# axiom_beta_sensor_cmv12000_v0_12_aa9cc54.net
KiCad netlist of a schematic drawn in EAGLE
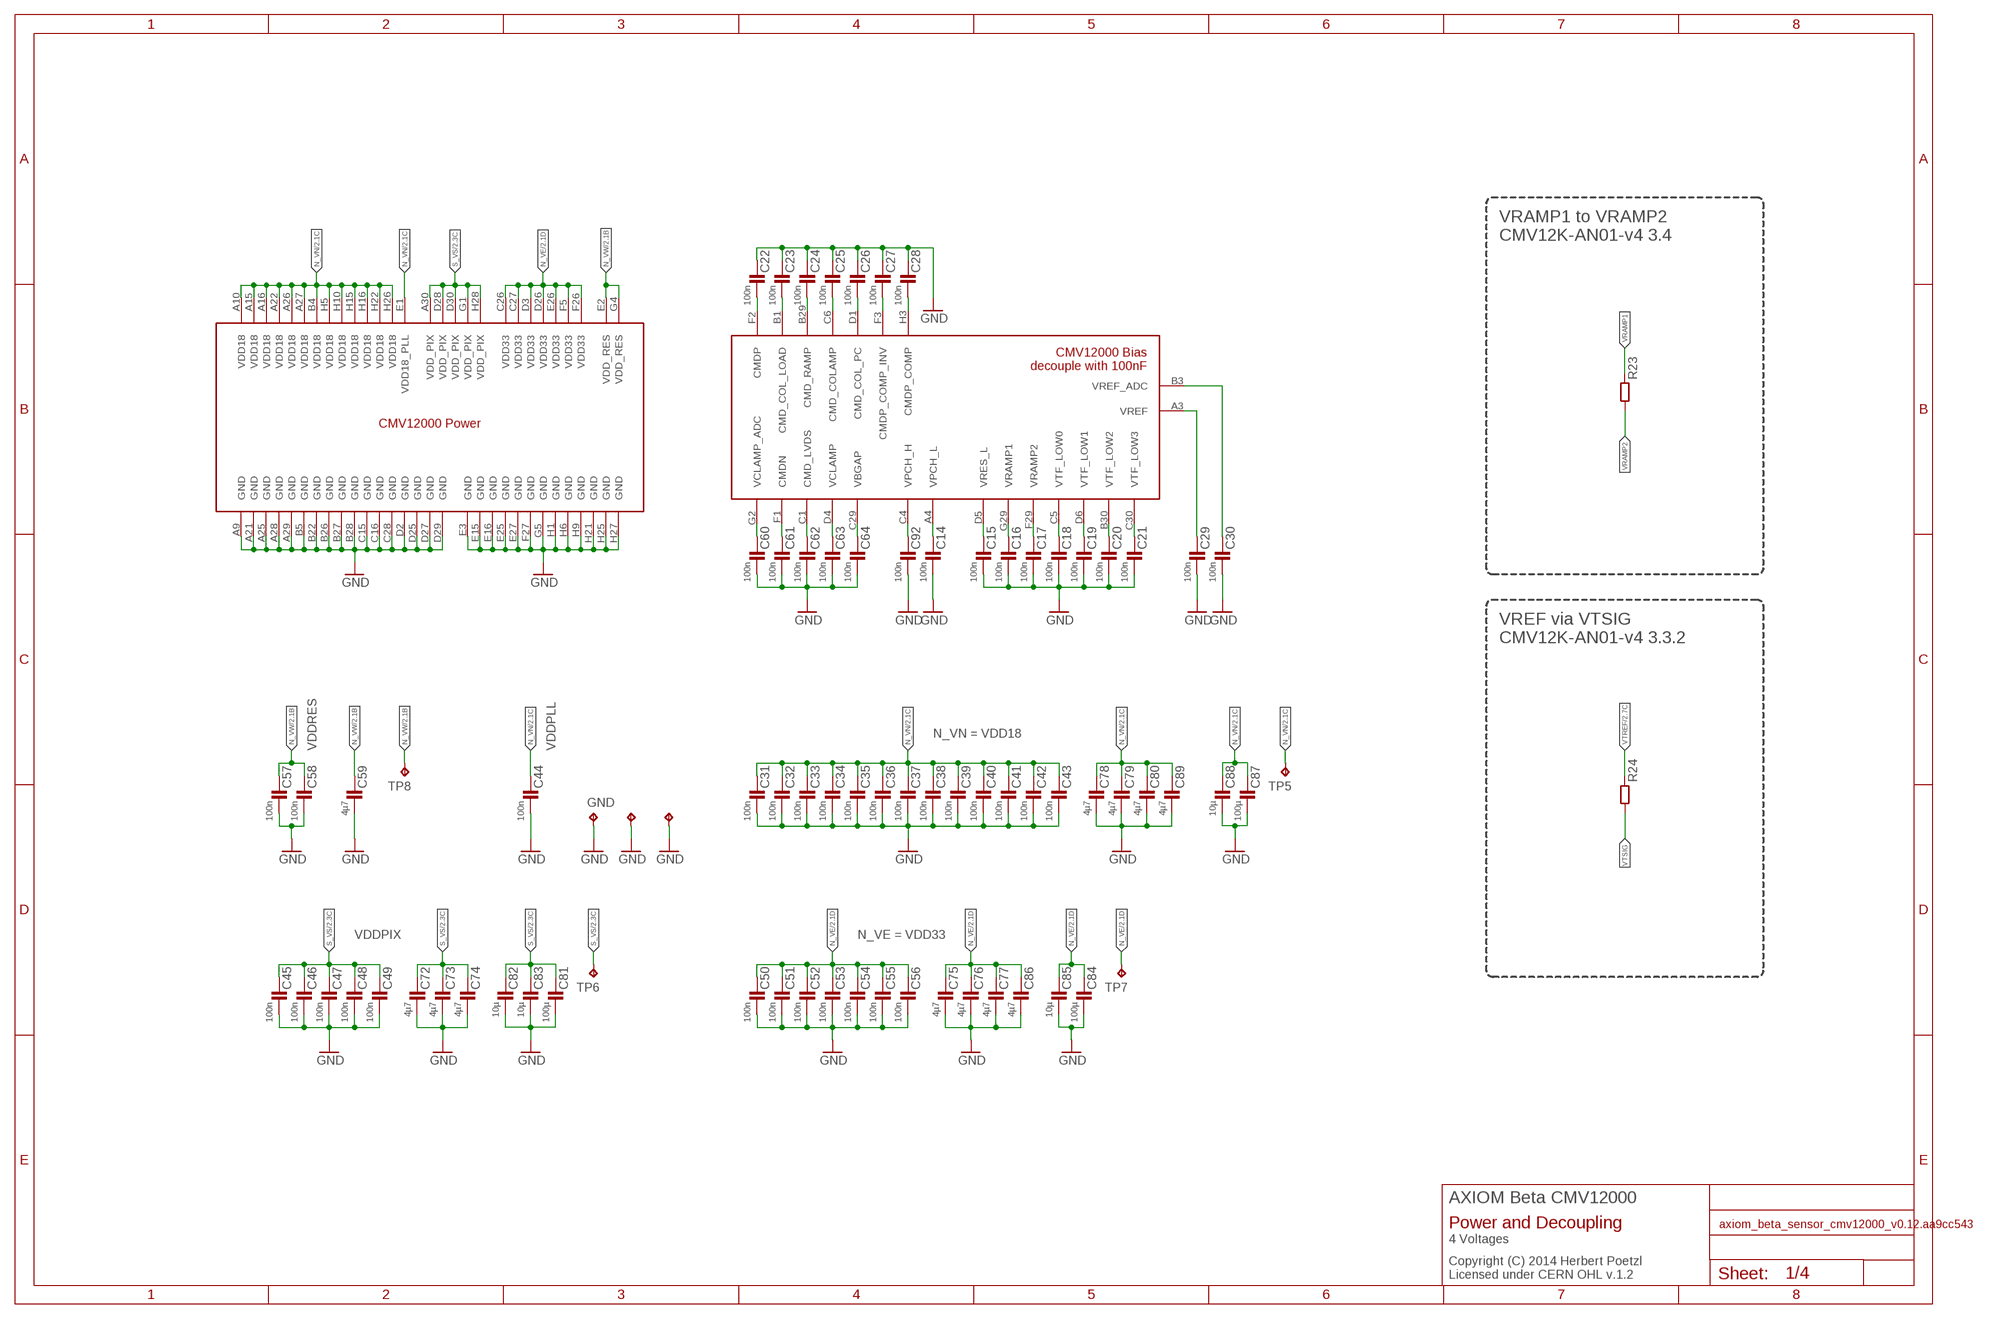
[diagram p0: schematic, sheet 1]
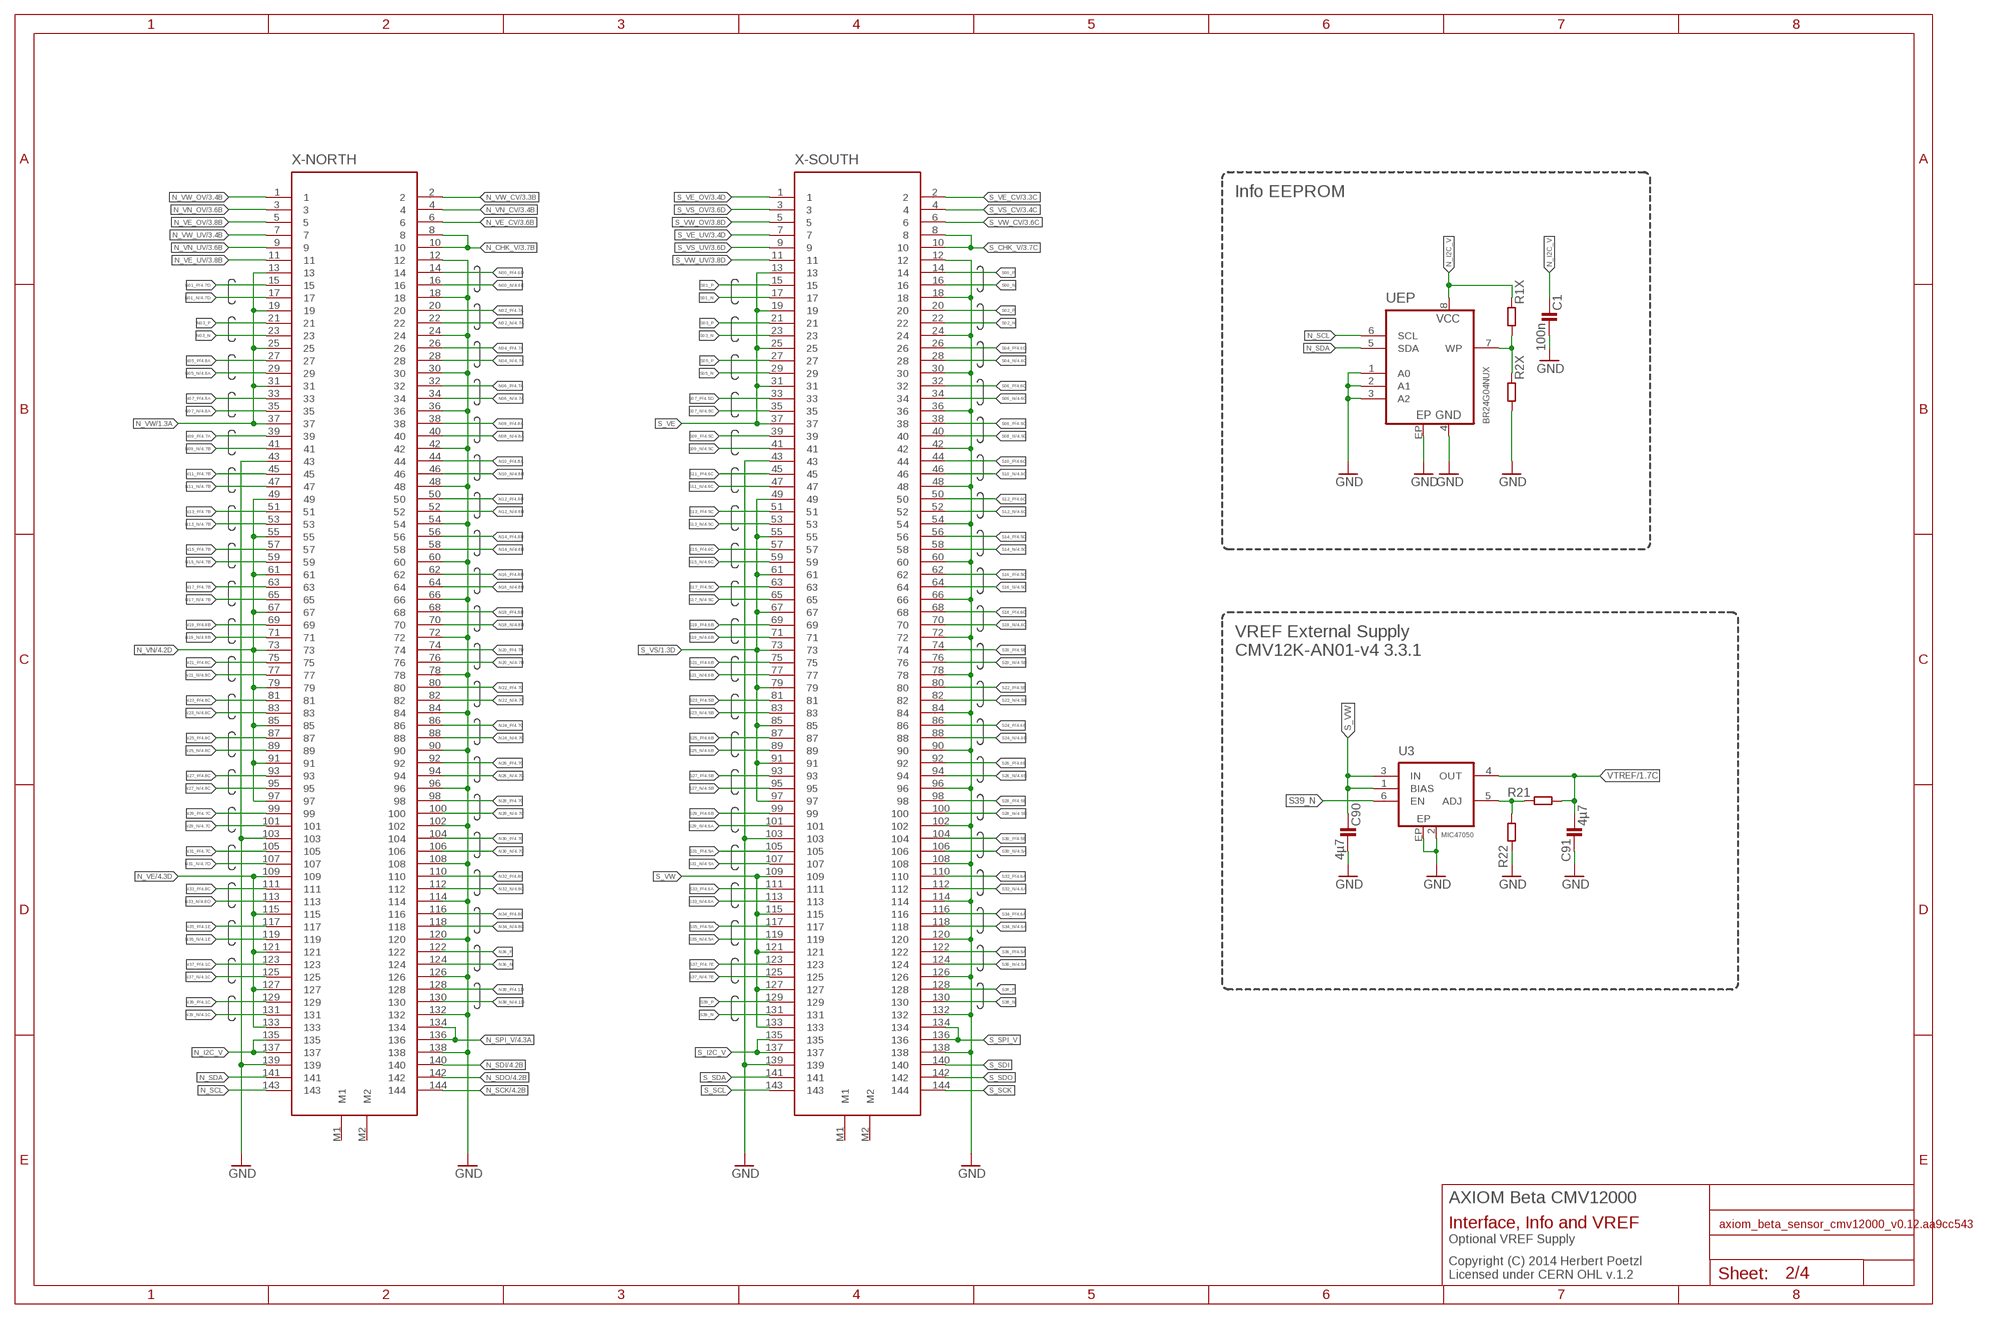
[diagram p1: schematic, sheet 2]
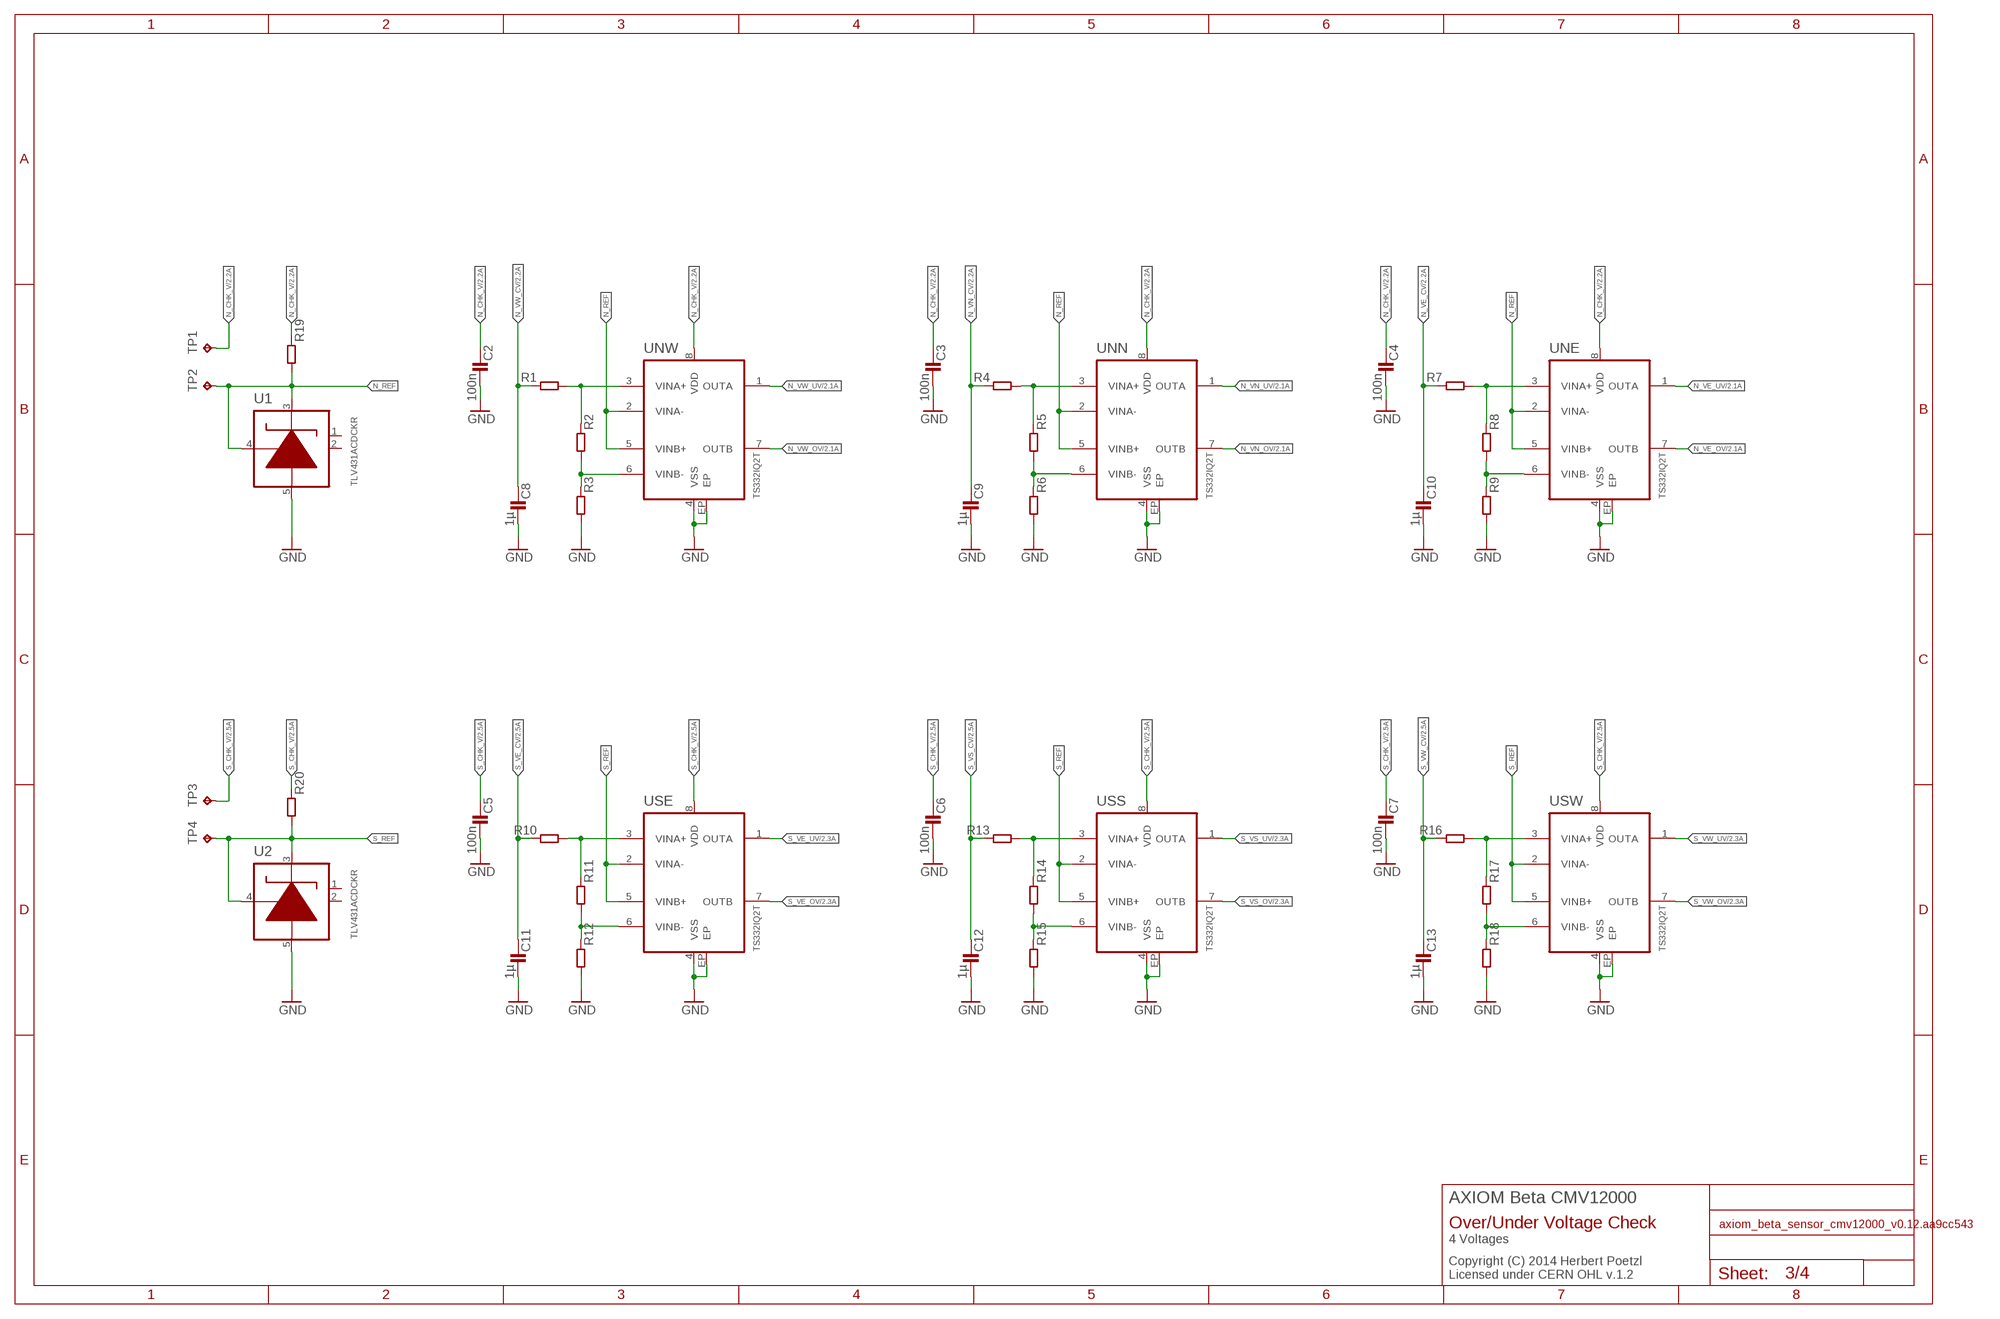
[diagram p2: schematic, sheet 3]
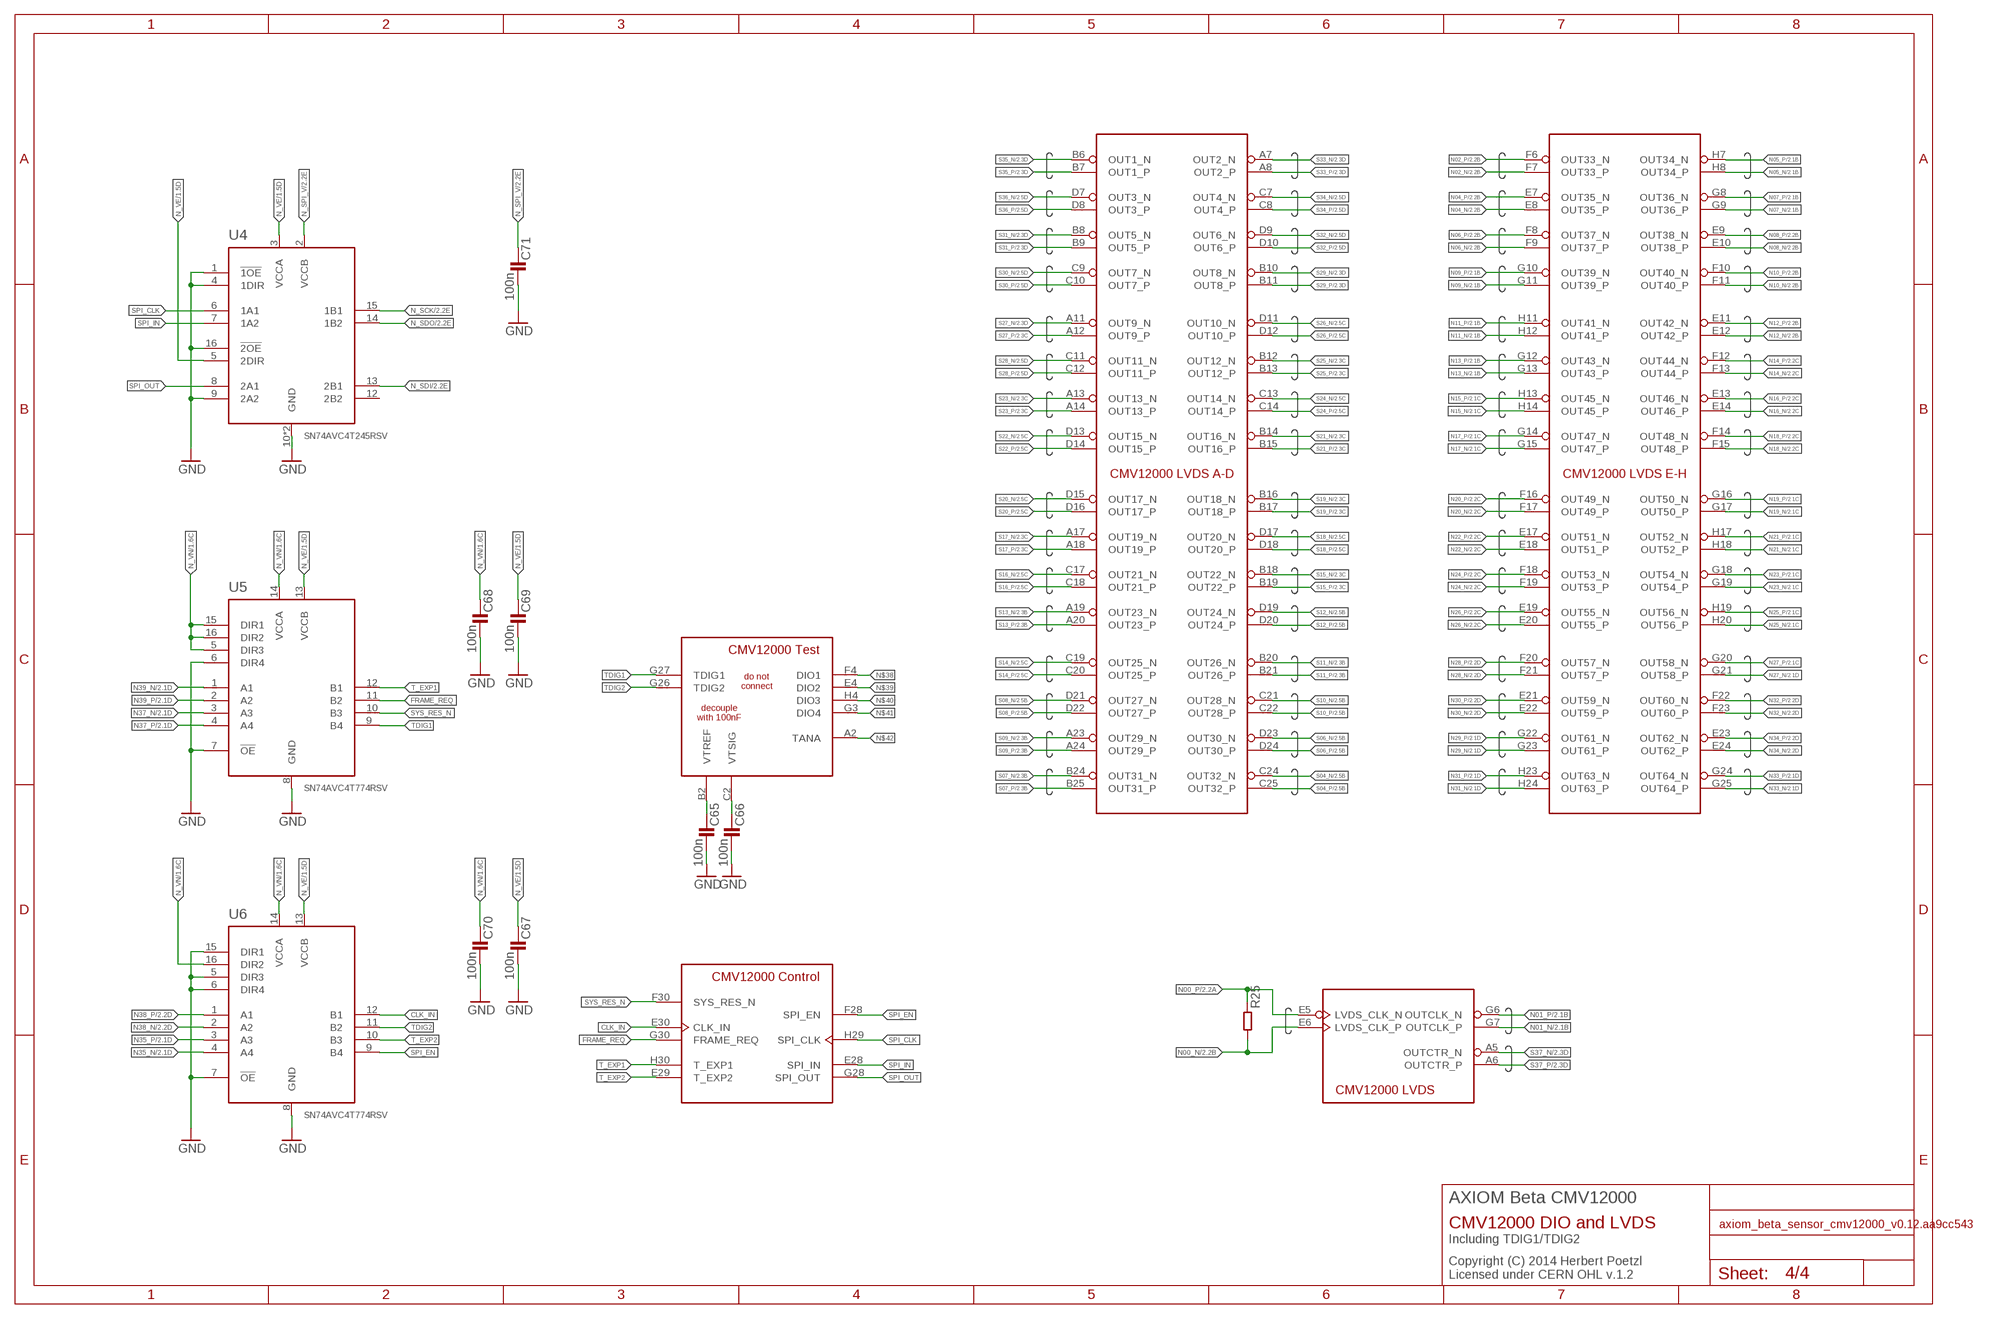
[diagram p3: schematic, sheet 4]

(export (version "E")
  (design (tool "Eeschema 10.0.6"))
  (components
    (comp (ref "C65")
      (value "100n")
      (footprint "eagle-import:0402-C")
      (libsource (lib "eagle-import") (part "C0402-C"))
    )
    (comp (ref "C66")
      (value "100n")
      (footprint "eagle-import:0402-C")
      (libsource (lib "eagle-import") (part "C0402-C"))
    )
    (comp (ref "C67")
      (value "100n")
      (footprint "eagle-import:0402-C")
      (libsource (lib "eagle-import") (part "C0402-C"))
    )
    (comp (ref "C68")
      (value "100n")
      (footprint "eagle-import:0402-C")
      (libsource (lib "eagle-import") (part "C0402-C"))
    )
    (comp (ref "C69")
      (value "100n")
      (footprint "eagle-import:0402-C")
      (libsource (lib "eagle-import") (part "C0402-C"))
    )
    (comp (ref "C70")
      (value "100n")
      (footprint "eagle-import:0402-C")
      (libsource (lib "eagle-import") (part "C0402-C"))
    )
    (comp (ref "C71")
      (value "100n")
      (footprint "eagle-import:0402-C")
      (libsource (lib "eagle-import") (part "C0402-C"))
    )
    (comp (ref "R25")
      (value "R0402-C")
      (footprint "eagle-import:0402-C")
      (libsource (lib "eagle-import") (part "R0402-C"))
    )
    (comp (ref "SENSOR")
      (value "CMV12000ANDON")
      (footprint "eagle-import:10-30-07-237-400T4")
      (libsource (lib "eagle-import") (part "CMV12000ANDON"))
    )
    (comp (ref "U4")
      (value "SN74AVC4T245RSV")
      (footprint "eagle-import:QFN40P185X265X55-16N")
      (libsource (lib "eagle-import") (part "SN74AVC4T245RSV"))
    )
    (comp (ref "U5")
      (value "SN74AVC4T774RSV")
      (footprint "eagle-import:QFN40P185X265X55-16N")
      (libsource (lib "eagle-import") (part "SN74AVC4T774RSV"))
    )
    (comp (ref "U6")
      (value "SN74AVC4T774RSV")
      (footprint "eagle-import:QFN40P185X265X55-16N")
      (libsource (lib "eagle-import") (part "SN74AVC4T774RSV"))
    )
    (comp (ref "C2")
      (value "100n")
      (footprint "eagle-import:0402-C")
      (libsource (lib "eagle-import") (part "C0402-C"))
    )
    (comp (ref "C3")
      (value "100n")
      (footprint "eagle-import:0402-C")
      (libsource (lib "eagle-import") (part "C0402-C"))
    )
    (comp (ref "C4")
      (value "100n")
      (footprint "eagle-import:0402-C")
      (libsource (lib "eagle-import") (part "C0402-C"))
    )
    (comp (ref "C5")
      (value "100n")
      (footprint "eagle-import:0402-C")
      (libsource (lib "eagle-import") (part "C0402-C"))
    )
    (comp (ref "C6")
      (value "100n")
      (footprint "eagle-import:0402-C")
      (libsource (lib "eagle-import") (part "C0402-C"))
    )
    (comp (ref "C7")
      (value "100n")
      (footprint "eagle-import:0402-C")
      (libsource (lib "eagle-import") (part "C0402-C"))
    )
    (comp (ref "C8")
      (value "1µ")
      (footprint "eagle-import:0402-C")
      (libsource (lib "eagle-import") (part "C0402-C"))
    )
    (comp (ref "C9")
      (value "1µ")
      (footprint "eagle-import:0402-C")
      (libsource (lib "eagle-import") (part "C0402-C"))
    )
    (comp (ref "C10")
      (value "1µ")
      (footprint "eagle-import:0402-C")
      (libsource (lib "eagle-import") (part "C0402-C"))
    )
    (comp (ref "C11")
      (value "1µ")
      (footprint "eagle-import:0402-C")
      (libsource (lib "eagle-import") (part "C0402-C"))
    )
    (comp (ref "C12")
      (value "1µ")
      (footprint "eagle-import:0402-C")
      (libsource (lib "eagle-import") (part "C0402-C"))
    )
    (comp (ref "C13")
      (value "1µ")
      (footprint "eagle-import:0402-C")
      (libsource (lib "eagle-import") (part "C0402-C"))
    )
    (comp (ref "R1")
      (value "R0402-C")
      (footprint "eagle-import:0402-C")
      (libsource (lib "eagle-import") (part "R0402-C"))
    )
    (comp (ref "R2")
      (value "R0402-C")
      (footprint "eagle-import:0402-C")
      (libsource (lib "eagle-import") (part "R0402-C"))
    )
    (comp (ref "R3")
      (value "R0402-C")
      (footprint "eagle-import:0402-C")
      (libsource (lib "eagle-import") (part "R0402-C"))
    )
    (comp (ref "R4")
      (value "R0402-C")
      (footprint "eagle-import:0402-C")
      (libsource (lib "eagle-import") (part "R0402-C"))
    )
    (comp (ref "R5")
      (value "R0402-C")
      (footprint "eagle-import:0402-C")
      (libsource (lib "eagle-import") (part "R0402-C"))
    )
    (comp (ref "R6")
      (value "R0402-C")
      (footprint "eagle-import:0402-C")
      (libsource (lib "eagle-import") (part "R0402-C"))
    )
    (comp (ref "R7")
      (value "R0402-C")
      (footprint "eagle-import:0402-C")
      (libsource (lib "eagle-import") (part "R0402-C"))
    )
    (comp (ref "R8")
      (value "R0402-C")
      (footprint "eagle-import:0402-C")
      (libsource (lib "eagle-import") (part "R0402-C"))
    )
    (comp (ref "R9")
      (value "R0402-C")
      (footprint "eagle-import:0402-C")
      (libsource (lib "eagle-import") (part "R0402-C"))
    )
    (comp (ref "R10")
      (value "R0402-C")
      (footprint "eagle-import:0402-C")
      (libsource (lib "eagle-import") (part "R0402-C"))
    )
    (comp (ref "R11")
      (value "R0402-C")
      (footprint "eagle-import:0402-C")
      (libsource (lib "eagle-import") (part "R0402-C"))
    )
    (comp (ref "R12")
      (value "R0402-C")
      (footprint "eagle-import:0402-C")
      (libsource (lib "eagle-import") (part "R0402-C"))
    )
    (comp (ref "R13")
      (value "R0402-C")
      (footprint "eagle-import:0402-C")
      (libsource (lib "eagle-import") (part "R0402-C"))
    )
    (comp (ref "R14")
      (value "R0402-C")
      (footprint "eagle-import:0402-C")
      (libsource (lib "eagle-import") (part "R0402-C"))
    )
    (comp (ref "R15")
      (value "R0402-C")
      (footprint "eagle-import:0402-C")
      (libsource (lib "eagle-import") (part "R0402-C"))
    )
    (comp (ref "R16")
      (value "R0402-C")
      (footprint "eagle-import:0402-C")
      (libsource (lib "eagle-import") (part "R0402-C"))
    )
    (comp (ref "R17")
      (value "R0402-C")
      (footprint "eagle-import:0402-C")
      (libsource (lib "eagle-import") (part "R0402-C"))
    )
    (comp (ref "R18")
      (value "R0402-C")
      (footprint "eagle-import:0402-C")
      (libsource (lib "eagle-import") (part "R0402-C"))
    )
    (comp (ref "R19")
      (value "R0402-C")
      (footprint "eagle-import:0402-C")
      (libsource (lib "eagle-import") (part "R0402-C"))
    )
    (comp (ref "R20")
      (value "R0402-C")
      (footprint "eagle-import:0402-C")
      (libsource (lib "eagle-import") (part "R0402-C"))
    )
    (comp (ref "TP1")
      (value "TPTP10R")
      (footprint "eagle-import:TP10R")
      (libsource (lib "eagle-import") (part "TPTP10R"))
    )
    (comp (ref "TP2")
      (value "TPTP10R")
      (footprint "eagle-import:TP10R")
      (libsource (lib "eagle-import") (part "TPTP10R"))
    )
    (comp (ref "TP3")
      (value "TPTP10R")
      (footprint "eagle-import:TP10R")
      (libsource (lib "eagle-import") (part "TPTP10R"))
    )
    (comp (ref "TP4")
      (value "TPTP10R")
      (footprint "eagle-import:TP10R")
      (libsource (lib "eagle-import") (part "TPTP10R"))
    )
    (comp (ref "U1")
      (value "TLV431ACDCKR")
      (footprint "eagle-import:SOT65P210X110-5N")
      (libsource (lib "eagle-import") (part "TLV431ACDCKR"))
    )
    (comp (ref "U2")
      (value "TLV431ACDCKR")
      (footprint "eagle-import:SOT65P210X110-5N")
      (libsource (lib "eagle-import") (part "TLV431ACDCKR"))
    )
    (comp (ref "UNE")
      (value "TS332IQ2T")
      (footprint "eagle-import:DFN200X200X100-9N")
      (libsource (lib "eagle-import") (part "TS332IQ2T"))
    )
    (comp (ref "UNN")
      (value "TS332IQ2T")
      (footprint "eagle-import:DFN200X200X100-9N")
      (libsource (lib "eagle-import") (part "TS332IQ2T"))
    )
    (comp (ref "UNW")
      (value "TS332IQ2T")
      (footprint "eagle-import:DFN200X200X100-9N")
      (libsource (lib "eagle-import") (part "TS332IQ2T"))
    )
    (comp (ref "USE")
      (value "TS332IQ2T")
      (footprint "eagle-import:DFN200X200X100-9N")
      (libsource (lib "eagle-import") (part "TS332IQ2T"))
    )
    (comp (ref "USS")
      (value "TS332IQ2T")
      (footprint "eagle-import:DFN200X200X100-9N")
      (libsource (lib "eagle-import") (part "TS332IQ2T"))
    )
    (comp (ref "USW")
      (value "TS332IQ2T")
      (footprint "eagle-import:DFN200X200X100-9N")
      (libsource (lib "eagle-import") (part "TS332IQ2T"))
    )
    (comp (ref "C1")
      (value "100n")
      (footprint "eagle-import:0402-C")
      (libsource (lib "eagle-import") (part "C0402-C"))
    )
    (comp (ref "C90")
      (value "4µ7")
      (footprint "eagle-import:0402-C")
      (libsource (lib "eagle-import") (part "C0402-C"))
    )
    (comp (ref "C91")
      (value "4µ7")
      (footprint "eagle-import:0402-C")
      (libsource (lib "eagle-import") (part "C0402-C"))
    )
    (comp (ref "R1X")
      (value "R0402-C")
      (footprint "eagle-import:0402-C")
      (libsource (lib "eagle-import") (part "R0402-C"))
    )
    (comp (ref "R2X")
      (value "R0402-C")
      (footprint "eagle-import:0402-C")
      (libsource (lib "eagle-import") (part "R0402-C"))
    )
    (comp (ref "R21")
      (value "R0402-C")
      (footprint "eagle-import:0402-C")
      (libsource (lib "eagle-import") (part "R0402-C"))
    )
    (comp (ref "R22")
      (value "R0402-C")
      (footprint "eagle-import:0402-C")
      (libsource (lib "eagle-import") (part "R0402-C"))
    )
    (comp (ref "U3")
      (value "MIC47050")
      (footprint "eagle-import:MLF-6")
      (libsource (lib "eagle-import") (part "MIC47050-ADJ"))
    )
    (comp (ref "UEP")
      (value "BR24G04NUX")
      (footprint "eagle-import:DFN200X300X100-9N")
      (libsource (lib "eagle-import") (part "BR24G04NUX"))
    )
    (comp (ref "X-NORTH")
      (value "FX10-144P")
      (footprint "eagle-import:FX10A-144P")
      (libsource (lib "eagle-import") (part "FX10-144P"))
    )
    (comp (ref "X-SOUTH")
      (value "FX10-144P")
      (footprint "eagle-import:FX10A-144P")
      (libsource (lib "eagle-import") (part "FX10-144P"))
    )
    (comp (ref "C14")
      (value "100n")
      (footprint "eagle-import:0402-C")
      (libsource (lib "eagle-import") (part "C0402-C"))
    )
    (comp (ref "C15")
      (value "100n")
      (footprint "eagle-import:0402-C")
      (libsource (lib "eagle-import") (part "C0402-C"))
    )
    (comp (ref "C16")
      (value "100n")
      (footprint "eagle-import:0402-C")
      (libsource (lib "eagle-import") (part "C0402-C"))
    )
    (comp (ref "C17")
      (value "100n")
      (footprint "eagle-import:0402-C")
      (libsource (lib "eagle-import") (part "C0402-C"))
    )
    (comp (ref "C18")
      (value "100n")
      (footprint "eagle-import:0402-C")
      (libsource (lib "eagle-import") (part "C0402-C"))
    )
    (comp (ref "C19")
      (value "100n")
      (footprint "eagle-import:0402-C")
      (libsource (lib "eagle-import") (part "C0402-C"))
    )
    (comp (ref "C20")
      (value "100n")
      (footprint "eagle-import:0402-C")
      (libsource (lib "eagle-import") (part "C0402-C"))
    )
    (comp (ref "C21")
      (value "100n")
      (footprint "eagle-import:0402-C")
      (libsource (lib "eagle-import") (part "C0402-C"))
    )
    (comp (ref "C22")
      (value "100n")
      (footprint "eagle-import:0402-C")
      (libsource (lib "eagle-import") (part "C0402-C"))
    )
    (comp (ref "C23")
      (value "100n")
      (footprint "eagle-import:0402-C")
      (libsource (lib "eagle-import") (part "C0402-C"))
    )
    (comp (ref "C24")
      (value "100n")
      (footprint "eagle-import:0402-C")
      (libsource (lib "eagle-import") (part "C0402-C"))
    )
    (comp (ref "C25")
      (value "100n")
      (footprint "eagle-import:0402-C")
      (libsource (lib "eagle-import") (part "C0402-C"))
    )
    (comp (ref "C26")
      (value "100n")
      (footprint "eagle-import:0402-C")
      (libsource (lib "eagle-import") (part "C0402-C"))
    )
    (comp (ref "C27")
      (value "100n")
      (footprint "eagle-import:0402-C")
      (libsource (lib "eagle-import") (part "C0402-C"))
    )
    (comp (ref "C28")
      (value "100n")
      (footprint "eagle-import:0402-C")
      (libsource (lib "eagle-import") (part "C0402-C"))
    )
    (comp (ref "C29")
      (value "100n")
      (footprint "eagle-import:0402-C")
      (libsource (lib "eagle-import") (part "C0402-C"))
    )
    (comp (ref "C30")
      (value "100n")
      (footprint "eagle-import:0402-C")
      (libsource (lib "eagle-import") (part "C0402-C"))
    )
    (comp (ref "C31")
      (value "100n")
      (footprint "eagle-import:0402-C")
      (libsource (lib "eagle-import") (part "C0402-C"))
    )
    (comp (ref "C32")
      (value "100n")
      (footprint "eagle-import:0402-C")
      (libsource (lib "eagle-import") (part "C0402-C"))
    )
    (comp (ref "C33")
      (value "100n")
      (footprint "eagle-import:0402-C")
      (libsource (lib "eagle-import") (part "C0402-C"))
    )
    (comp (ref "C34")
      (value "100n")
      (footprint "eagle-import:0402-C")
      (libsource (lib "eagle-import") (part "C0402-C"))
    )
    (comp (ref "C35")
      (value "100n")
      (footprint "eagle-import:0402-C")
      (libsource (lib "eagle-import") (part "C0402-C"))
    )
    (comp (ref "C36")
      (value "100n")
      (footprint "eagle-import:0402-C")
      (libsource (lib "eagle-import") (part "C0402-C"))
    )
    (comp (ref "C37")
      (value "100n")
      (footprint "eagle-import:0402-C")
      (libsource (lib "eagle-import") (part "C0402-C"))
    )
    (comp (ref "C38")
      (value "100n")
      (footprint "eagle-import:0402-C")
      (libsource (lib "eagle-import") (part "C0402-C"))
    )
    (comp (ref "C39")
      (value "100n")
      (footprint "eagle-import:0402-C")
      (libsource (lib "eagle-import") (part "C0402-C"))
    )
    (comp (ref "C40")
      (value "100n")
      (footprint "eagle-import:0402-C")
      (libsource (lib "eagle-import") (part "C0402-C"))
    )
    (comp (ref "C41")
      (value "100n")
      (footprint "eagle-import:0402-C")
      (libsource (lib "eagle-import") (part "C0402-C"))
    )
    (comp (ref "C42")
      (value "100n")
      (footprint "eagle-import:0402-C")
      (libsource (lib "eagle-import") (part "C0402-C"))
    )
    (comp (ref "C43")
      (value "100n")
      (footprint "eagle-import:0402-C")
      (libsource (lib "eagle-import") (part "C0402-C"))
    )
    (comp (ref "C44")
      (value "100n")
      (footprint "eagle-import:0402-C")
      (libsource (lib "eagle-import") (part "C0402-C"))
    )
    (comp (ref "C45")
      (value "100n")
      (footprint "eagle-import:0402-C")
      (libsource (lib "eagle-import") (part "C0402-C"))
    )
    (comp (ref "C46")
      (value "100n")
      (footprint "eagle-import:0402-C")
      (libsource (lib "eagle-import") (part "C0402-C"))
    )
    (comp (ref "C47")
      (value "100n")
      (footprint "eagle-import:0402-C")
      (libsource (lib "eagle-import") (part "C0402-C"))
    )
    (comp (ref "C48")
      (value "100n")
      (footprint "eagle-import:0402-C")
      (libsource (lib "eagle-import") (part "C0402-C"))
    )
    (comp (ref "C49")
      (value "100n")
      (footprint "eagle-import:0402-C")
      (libsource (lib "eagle-import") (part "C0402-C"))
    )
    (comp (ref "C50")
      (value "100n")
      (footprint "eagle-import:0402-C")
      (libsource (lib "eagle-import") (part "C0402-C"))
    )
    (comp (ref "C51")
      (value "100n")
      (footprint "eagle-import:0402-C")
      (libsource (lib "eagle-import") (part "C0402-C"))
    )
    (comp (ref "C52")
      (value "100n")
      (footprint "eagle-import:0402-C")
      (libsource (lib "eagle-import") (part "C0402-C"))
    )
    (comp (ref "C53")
      (value "100n")
      (footprint "eagle-import:0402-C")
      (libsource (lib "eagle-import") (part "C0402-C"))
    )
    (comp (ref "C54")
      (value "100n")
      (footprint "eagle-import:0402-C")
      (libsource (lib "eagle-import") (part "C0402-C"))
    )
    (comp (ref "C55")
      (value "100n")
      (footprint "eagle-import:0402-C")
      (libsource (lib "eagle-import") (part "C0402-C"))
    )
    (comp (ref "C56")
      (value "100n")
      (footprint "eagle-import:0402-C")
      (libsource (lib "eagle-import") (part "C0402-C"))
    )
    (comp (ref "C57")
      (value "100n")
      (footprint "eagle-import:0402-C")
      (libsource (lib "eagle-import") (part "C0402-C"))
    )
    (comp (ref "C58")
      (value "100n")
      (footprint "eagle-import:0402-C")
      (libsource (lib "eagle-import") (part "C0402-C"))
    )
    (comp (ref "C59")
      (value "4µ7")
      (footprint "eagle-import:0402-C")
      (libsource (lib "eagle-import") (part "C0402-C"))
    )
    (comp (ref "C60")
      (value "100n")
      (footprint "eagle-import:0402-C")
      (libsource (lib "eagle-import") (part "C0402-C"))
    )
    (comp (ref "C61")
      (value "100n")
      (footprint "eagle-import:0402-C")
      (libsource (lib "eagle-import") (part "C0402-C"))
    )
    (comp (ref "C62")
      (value "100n")
      (footprint "eagle-import:0402-C")
      (libsource (lib "eagle-import") (part "C0402-C"))
    )
    (comp (ref "C63")
      (value "100n")
      (footprint "eagle-import:0402-C")
      (libsource (lib "eagle-import") (part "C0402-C"))
    )
    (comp (ref "C64")
      (value "100n")
      (footprint "eagle-import:0402-C")
      (libsource (lib "eagle-import") (part "C0402-C"))
    )
    (comp (ref "C72")
      (value "4µ7")
      (footprint "eagle-import:0402-B")
      (libsource (lib "eagle-import") (part "C0402-B"))
    )
    (comp (ref "C73")
      (value "4µ7")
      (footprint "eagle-import:0402-C")
      (libsource (lib "eagle-import") (part "C0402-C"))
    )
    (comp (ref "C74")
      (value "4µ7")
      (footprint "eagle-import:0402-C")
      (libsource (lib "eagle-import") (part "C0402-C"))
    )
    (comp (ref "C75")
      (value "4µ7")
      (footprint "eagle-import:0402-C")
      (libsource (lib "eagle-import") (part "C0402-C"))
    )
    (comp (ref "C76")
      (value "4µ7")
      (footprint "eagle-import:0402-C")
      (libsource (lib "eagle-import") (part "C0402-C"))
    )
    (comp (ref "C77")
      (value "4µ7")
      (footprint "eagle-import:0402-B")
      (libsource (lib "eagle-import") (part "C0402-B"))
    )
    (comp (ref "C78")
      (value "4µ7")
      (footprint "eagle-import:0402-B")
      (libsource (lib "eagle-import") (part "C0402-B"))
    )
    (comp (ref "C79")
      (value "4µ7")
      (footprint "eagle-import:0402-C")
      (libsource (lib "eagle-import") (part "C0402-C"))
    )
    (comp (ref "C80")
      (value "4µ7")
      (footprint "eagle-import:0402-C")
      (libsource (lib "eagle-import") (part "C0402-C"))
    )
    (comp (ref "C81")
      (value "100µ")
      (footprint "eagle-import:1206-B")
      (libsource (lib "eagle-import") (part "C1206-B"))
    )
    (comp (ref "C82")
      (value "10µ")
      (footprint "eagle-import:0603-C")
      (libsource (lib "eagle-import") (part "C0603-C"))
    )
    (comp (ref "C83")
      (value "10µ")
      (footprint "eagle-import:0603-C")
      (libsource (lib "eagle-import") (part "C0603-C"))
    )
    (comp (ref "C84")
      (value "100µ")
      (footprint "eagle-import:1206-B")
      (libsource (lib "eagle-import") (part "C1206-B"))
    )
    (comp (ref "C85")
      (value "10µ")
      (footprint "eagle-import:0603-C")
      (libsource (lib "eagle-import") (part "C0603-C"))
    )
    (comp (ref "C86")
      (value "4µ7")
      (footprint "eagle-import:0402-C")
      (libsource (lib "eagle-import") (part "C0402-C"))
    )
    (comp (ref "C87")
      (value "100µ")
      (footprint "eagle-import:1206-B")
      (libsource (lib "eagle-import") (part "C1206-B"))
    )
    (comp (ref "C88")
      (value "10µ")
      (footprint "eagle-import:0603-C")
      (libsource (lib "eagle-import") (part "C0603-C"))
    )
    (comp (ref "C89")
      (value "4µ7")
      (footprint "eagle-import:0402-C")
      (libsource (lib "eagle-import") (part "C0402-C"))
    )
    (comp (ref "C92")
      (value "100n")
      (footprint "eagle-import:0402-C")
      (libsource (lib "eagle-import") (part "C0402-C"))
    )
    (comp (ref "GND")
      (value "TPTP10R")
      (footprint "eagle-import:TP10R")
      (libsource (lib "eagle-import") (part "TPTP10R"))
    )
    (comp (ref "GND75")
      (value "TPTP10R")
      (footprint "eagle-import:TP10R")
      (libsource (lib "eagle-import") (part "TPTP10R"))
    )
    (comp (ref "GND77")
      (value "TPTP10R")
      (footprint "eagle-import:TP10R")
      (libsource (lib "eagle-import") (part "TPTP10R"))
    )
    (comp (ref "R23")
      (value "R0402-C")
      (footprint "eagle-import:0402-C")
      (libsource (lib "eagle-import") (part "R0402-C"))
    )
    (comp (ref "R24")
      (value "R0402-C")
      (footprint "eagle-import:0402-C")
      (libsource (lib "eagle-import") (part "R0402-C"))
    )
    (comp (ref "TP5")
      (value "TPTP10R")
      (footprint "eagle-import:TP10R")
      (libsource (lib "eagle-import") (part "TPTP10R"))
    )
    (comp (ref "TP6")
      (value "TPTP10R")
      (footprint "eagle-import:TP10R")
      (libsource (lib "eagle-import") (part "TPTP10R"))
    )
    (comp (ref "TP7")
      (value "TPTP10R")
      (footprint "eagle-import:TP10R")
      (libsource (lib "eagle-import") (part "TPTP10R"))
    )
    (comp (ref "TP8")
      (value "TPTP10R")
      (footprint "eagle-import:TP10R")
      (libsource (lib "eagle-import") (part "TPTP10R"))
    )
  )
  (nets
    (net (code "1") (name "CLK_IN") (class "Default")
      (node (ref "SENSOR") (pin "E30") (pinfunction "CLK_IN_E30") (pintype "input"))
      (node (ref "U6") (pin "12") (pinfunction "B1_12") (pintype "bidirectional"))
    )
    (net (code "2") (name "FRAME_REQ") (class "Default")
      (node (ref "SENSOR") (pin "G30") (pinfunction "FRAME_REQ_G30") (pintype "input"))
      (node (ref "U5") (pin "11") (pinfunction "B2_11") (pintype "bidirectional"))
    )
    (net (code "3") (name "GND") (class "Default")
      (node (ref "C1") (pin "2") (pinfunction "2_2") (pintype "passive"))
      (node (ref "C10") (pin "2") (pinfunction "2_2") (pintype "passive"))
      (node (ref "C11") (pin "2") (pinfunction "2_2") (pintype "passive"))
      (node (ref "C12") (pin "2") (pinfunction "2_2") (pintype "passive"))
      (node (ref "C13") (pin "2") (pinfunction "2_2") (pintype "passive"))
      (node (ref "C14") (pin "2") (pinfunction "2_2") (pintype "passive"))
      (node (ref "C15") (pin "2") (pinfunction "2_2") (pintype "passive"))
      (node (ref "C16") (pin "2") (pinfunction "2_2") (pintype "passive"))
      (node (ref "C17") (pin "2") (pinfunction "2_2") (pintype "passive"))
      (node (ref "C18") (pin "2") (pinfunction "2_2") (pintype "passive"))
      (node (ref "C19") (pin "2") (pinfunction "2_2") (pintype "passive"))
      (node (ref "C2") (pin "2") (pinfunction "2_2") (pintype "passive"))
      (node (ref "C20") (pin "2") (pinfunction "2_2") (pintype "passive"))
      (node (ref "C21") (pin "2") (pinfunction "2_2") (pintype "passive"))
      (node (ref "C22") (pin "1") (pinfunction "1_1") (pintype "passive"))
      (node (ref "C23") (pin "1") (pinfunction "1_1") (pintype "passive"))
      (node (ref "C24") (pin "1") (pinfunction "1_1") (pintype "passive"))
      (node (ref "C25") (pin "1") (pinfunction "1_1") (pintype "passive"))
      (node (ref "C26") (pin "1") (pinfunction "1_1") (pintype "passive"))
      (node (ref "C27") (pin "1") (pinfunction "1_1") (pintype "passive"))
      (node (ref "C28") (pin "1") (pinfunction "1_1") (pintype "passive"))
      (node (ref "C29") (pin "2") (pinfunction "2_2") (pintype "passive"))
      (node (ref "C3") (pin "2") (pinfunction "2_2") (pintype "passive"))
      (node (ref "C30") (pin "2") (pinfunction "2_2") (pintype "passive"))
      (node (ref "C31") (pin "2") (pinfunction "2_2") (pintype "passive"))
      (node (ref "C32") (pin "2") (pinfunction "2_2") (pintype "passive"))
      (node (ref "C33") (pin "2") (pinfunction "2_2") (pintype "passive"))
      (node (ref "C34") (pin "2") (pinfunction "2_2") (pintype "passive"))
      (node (ref "C35") (pin "2") (pinfunction "2_2") (pintype "passive"))
      (node (ref "C36") (pin "2") (pinfunction "2_2") (pintype "passive"))
      (node (ref "C37") (pin "2") (pinfunction "2_2") (pintype "passive"))
      (node (ref "C38") (pin "2") (pinfunction "2_2") (pintype "passive"))
      (node (ref "C39") (pin "2") (pinfunction "2_2") (pintype "passive"))
      (node (ref "C4") (pin "2") (pinfunction "2_2") (pintype "passive"))
      (node (ref "C40") (pin "2") (pinfunction "2_2") (pintype "passive"))
      (node (ref "C41") (pin "2") (pinfunction "2_2") (pintype "passive"))
      (node (ref "C42") (pin "2") (pinfunction "2_2") (pintype "passive"))
      (node (ref "C43") (pin "2") (pinfunction "2_2") (pintype "passive"))
      (node (ref "C44") (pin "2") (pinfunction "2_2") (pintype "passive"))
      (node (ref "C45") (pin "2") (pinfunction "2_2") (pintype "passive"))
      (node (ref "C46") (pin "2") (pinfunction "2_2") (pintype "passive"))
      (node (ref "C47") (pin "2") (pinfunction "2_2") (pintype "passive"))
      (node (ref "C48") (pin "2") (pinfunction "2_2") (pintype "passive"))
      (node (ref "C49") (pin "2") (pinfunction "2_2") (pintype "passive"))
      (node (ref "C5") (pin "2") (pinfunction "2_2") (pintype "passive"))
      (node (ref "C50") (pin "2") (pinfunction "2_2") (pintype "passive"))
      (node (ref "C51") (pin "2") (pinfunction "2_2") (pintype "passive"))
      (node (ref "C52") (pin "2") (pinfunction "2_2") (pintype "passive"))
      (node (ref "C53") (pin "2") (pinfunction "2_2") (pintype "passive"))
      (node (ref "C54") (pin "2") (pinfunction "2_2") (pintype "passive"))
      (node (ref "C55") (pin "2") (pinfunction "2_2") (pintype "passive"))
      (node (ref "C56") (pin "2") (pinfunction "2_2") (pintype "passive"))
      (node (ref "C57") (pin "2") (pinfunction "2_2") (pintype "passive"))
      (node (ref "C58") (pin "2") (pinfunction "2_2") (pintype "passive"))
      (node (ref "C59") (pin "2") (pinfunction "2_2") (pintype "passive"))
      (node (ref "C6") (pin "2") (pinfunction "2_2") (pintype "passive"))
      (node (ref "C60") (pin "2") (pinfunction "2_2") (pintype "passive"))
      (node (ref "C61") (pin "2") (pinfunction "2_2") (pintype "passive"))
      (node (ref "C62") (pin "2") (pinfunction "2_2") (pintype "passive"))
      (node (ref "C63") (pin "2") (pinfunction "2_2") (pintype "passive"))
      (node (ref "C64") (pin "2") (pinfunction "2_2") (pintype "passive"))
      (node (ref "C65") (pin "2") (pinfunction "2_2") (pintype "passive"))
      (node (ref "C66") (pin "2") (pinfunction "2_2") (pintype "passive"))
      (node (ref "C67") (pin "2") (pinfunction "2_2") (pintype "passive"))
      (node (ref "C68") (pin "2") (pinfunction "2_2") (pintype "passive"))
      (node (ref "C69") (pin "2") (pinfunction "2_2") (pintype "passive"))
      (node (ref "C7") (pin "2") (pinfunction "2_2") (pintype "passive"))
      (node (ref "C70") (pin "2") (pinfunction "2_2") (pintype "passive"))
      (node (ref "C71") (pin "2") (pinfunction "2_2") (pintype "passive"))
      (node (ref "C72") (pin "2") (pinfunction "2_2") (pintype "passive"))
      (node (ref "C73") (pin "2") (pinfunction "2_2") (pintype "passive"))
      (node (ref "C74") (pin "2") (pinfunction "2_2") (pintype "passive"))
      (node (ref "C75") (pin "2") (pinfunction "2_2") (pintype "passive"))
      (node (ref "C76") (pin "2") (pinfunction "2_2") (pintype "passive"))
      (node (ref "C77") (pin "2") (pinfunction "2_2") (pintype "passive"))
      (node (ref "C78") (pin "2") (pinfunction "2_2") (pintype "passive"))
      (node (ref "C79") (pin "2") (pinfunction "2_2") (pintype "passive"))
      (node (ref "C8") (pin "2") (pinfunction "2_2") (pintype "passive"))
      (node (ref "C80") (pin "2") (pinfunction "2_2") (pintype "passive"))
      (node (ref "C81") (pin "2") (pinfunction "2_2") (pintype "passive"))
      (node (ref "C82") (pin "2") (pinfunction "2_2") (pintype "passive"))
      (node (ref "C83") (pin "2") (pinfunction "2_2") (pintype "passive"))
      (node (ref "C84") (pin "2") (pinfunction "2_2") (pintype "passive"))
      (node (ref "C85") (pin "2") (pinfunction "2_2") (pintype "passive"))
      (node (ref "C86") (pin "2") (pinfunction "2_2") (pintype "passive"))
      (node (ref "C87") (pin "2") (pinfunction "2_2") (pintype "passive"))
      (node (ref "C88") (pin "2") (pinfunction "2_2") (pintype "passive"))
      (node (ref "C89") (pin "2") (pinfunction "2_2") (pintype "passive"))
      (node (ref "C9") (pin "2") (pinfunction "2_2") (pintype "passive"))
      (node (ref "C90") (pin "2") (pinfunction "2_2") (pintype "passive"))
      (node (ref "C91") (pin "1") (pinfunction "1_1") (pintype "passive"))
      (node (ref "C92") (pin "2") (pinfunction "2_2") (pintype "passive"))
      (node (ref "GND") (pin "TP") (pinfunction "TP_TP") (pintype "input"))
      (node (ref "GND75") (pin "TP") (pinfunction "TP_TP") (pintype "input"))
      (node (ref "GND77") (pin "TP") (pinfunction "TP_TP") (pintype "input"))
      (node (ref "R12") (pin "2") (pinfunction "2_2") (pintype "passive"))
      (node (ref "R15") (pin "2") (pinfunction "2_2") (pintype "passive"))
      (node (ref "R18") (pin "2") (pinfunction "2_2") (pintype "passive"))
      (node (ref "R22") (pin "1") (pinfunction "1_1") (pintype "passive"))
      (node (ref "R2X") (pin "2") (pinfunction "2_2") (pintype "passive"))
      (node (ref "R3") (pin "2") (pinfunction "2_2") (pintype "passive"))
      (node (ref "R6") (pin "2") (pinfunction "2_2") (pintype "passive"))
      (node (ref "R9") (pin "2") (pinfunction "2_2") (pintype "passive"))
      (node (ref "SENSOR") (pin "A21") (pinfunction "GND_A21") (pintype "power_in"))
      (node (ref "SENSOR") (pin "A25") (pinfunction "GND_A25") (pintype "power_in"))
      (node (ref "SENSOR") (pin "A28") (pinfunction "GND_A28") (pintype "power_in"))
      (node (ref "SENSOR") (pin "A29") (pinfunction "GND_A29") (pintype "power_in"))
      (node (ref "SENSOR") (pin "A9") (pinfunction "GND_A9") (pintype "power_in"))
      (node (ref "SENSOR") (pin "B22") (pinfunction "GND_B22") (pintype "power_in"))
      (node (ref "SENSOR") (pin "B26") (pinfunction "GND_B26") (pintype "power_in"))
      (node (ref "SENSOR") (pin "B27") (pinfunction "GND_B27") (pintype "power_in"))
      (node (ref "SENSOR") (pin "B28") (pinfunction "GND_B28") (pintype "power_in"))
      (node (ref "SENSOR") (pin "B5") (pinfunction "GND_B5") (pintype "power_in"))
      (node (ref "SENSOR") (pin "C15") (pinfunction "GND_C15") (pintype "power_in"))
      (node (ref "SENSOR") (pin "C16") (pinfunction "GND_C16") (pintype "power_in"))
      (node (ref "SENSOR") (pin "C28") (pinfunction "GND_C28") (pintype "power_in"))
      (node (ref "SENSOR") (pin "D2") (pinfunction "GND_D2") (pintype "power_in"))
      (node (ref "SENSOR") (pin "D25") (pinfunction "GND_D25") (pintype "power_in"))
      (node (ref "SENSOR") (pin "D27") (pinfunction "GND_D27") (pintype "power_in"))
      (node (ref "SENSOR") (pin "D29") (pinfunction "GND_D29") (pintype "power_in"))
      (node (ref "SENSOR") (pin "E15") (pinfunction "GND_E15") (pintype "power_in"))
      (node (ref "SENSOR") (pin "E16") (pinfunction "GND_E16") (pintype "power_in"))
      (node (ref "SENSOR") (pin "E25") (pinfunction "GND_E25") (pintype "power_in"))
      (node (ref "SENSOR") (pin "E27") (pinfunction "GND_E27") (pintype "power_in"))
      (node (ref "SENSOR") (pin "E3") (pinfunction "GND_E3") (pintype "power_in"))
      (node (ref "SENSOR") (pin "F27") (pinfunction "GND_F27") (pintype "power_in"))
      (node (ref "SENSOR") (pin "G5") (pinfunction "GND_G5") (pintype "power_in"))
      (node (ref "SENSOR") (pin "H1") (pinfunction "GND_H1") (pintype "power_in"))
      (node (ref "SENSOR") (pin "H21") (pinfunction "GND_H21") (pintype "power_in"))
      (node (ref "SENSOR") (pin "H25") (pinfunction "GND_H25") (pintype "power_in"))
      (node (ref "SENSOR") (pin "H27") (pinfunction "GND_H27") (pintype "power_in"))
      (node (ref "SENSOR") (pin "H6") (pinfunction "GND_H6") (pintype "power_in"))
      (node (ref "SENSOR") (pin "H9") (pinfunction "GND_H9") (pintype "power_in"))
      (node (ref "U1") (pin "5") (pinfunction "ANODE_5") (pintype "input"))
      (node (ref "U2") (pin "5") (pinfunction "ANODE_5") (pintype "input"))
      (node (ref "U3") (pin "2") (pinfunction "GND_2") (pintype "power_in"))
      (node (ref "U3") (pin "EP") (pinfunction "EP_EP") (pintype "power_in"))
      (node (ref "U4") (pin "1") (pinfunction "~{1OE}_1") (pintype "input"))
      (node (ref "U4") (pin "10") (pinfunction "GND_10") (pintype "passive"))
      (node (ref "U4") (pin "11") (pinfunction "GND_11") (pintype "passive"))
      (node (ref "U4") (pin "16") (pinfunction "~{2OE}_16") (pintype "input"))
      (node (ref "U4") (pin "4") (pinfunction "1DIR_4") (pintype "input"))
      (node (ref "U4") (pin "9") (pinfunction "2A2_9") (pintype "output"))
      (node (ref "U5") (pin "6") (pinfunction "DIR4_6") (pintype "input"))
      (node (ref "U5") (pin "7") (pinfunction "~{OE}_7") (pintype "input"))
      (node (ref "U5") (pin "8") (pinfunction "GND_8") (pintype "passive"))
      (node (ref "U6") (pin "15") (pinfunction "DIR1_15") (pintype "input"))
      (node (ref "U6") (pin "5") (pinfunction "DIR3_5") (pintype "input"))
      (node (ref "U6") (pin "6") (pinfunction "DIR4_6") (pintype "input"))
      (node (ref "U6") (pin "7") (pinfunction "~{OE}_7") (pintype "input"))
      (node (ref "U6") (pin "8") (pinfunction "GND_8") (pintype "passive"))
      (node (ref "UEP") (pin "1") (pinfunction "A0_1") (pintype "input"))
      (node (ref "UEP") (pin "2") (pinfunction "A1_2") (pintype "input"))
      (node (ref "UEP") (pin "3") (pinfunction "A2_3") (pintype "input"))
      (node (ref "UEP") (pin "4") (pinfunction "GND_4") (pintype "passive"))
      (node (ref "UEP") (pin "EP") (pinfunction "EP_EP") (pintype "passive"))
      (node (ref "UNE") (pin "4") (pinfunction "VSS_4") (pintype "power_in"))
      (node (ref "UNE") (pin "EP") (pinfunction "EP_EP") (pintype "passive"))
      (node (ref "UNN") (pin "4") (pinfunction "VSS_4") (pintype "power_in"))
      (node (ref "UNN") (pin "EP") (pinfunction "EP_EP") (pintype "passive"))
      (node (ref "UNW") (pin "4") (pinfunction "VSS_4") (pintype "power_in"))
      (node (ref "UNW") (pin "EP") (pinfunction "EP_EP") (pintype "passive"))
      (node (ref "USE") (pin "4") (pinfunction "VSS_4") (pintype "power_in"))
      (node (ref "USE") (pin "EP") (pinfunction "EP_EP") (pintype "passive"))
      (node (ref "USS") (pin "4") (pinfunction "VSS_4") (pintype "power_in"))
      (node (ref "USS") (pin "EP") (pinfunction "EP_EP") (pintype "passive"))
      (node (ref "USW") (pin "4") (pinfunction "VSS_4") (pintype "power_in"))
      (node (ref "USW") (pin "EP") (pinfunction "EP_EP") (pintype "passive"))
      (node (ref "X-NORTH") (pin "102") (pinfunction "102_102") (pintype "bidirectional"))
      (node (ref "X-NORTH") (pin "103") (pinfunction "103_103") (pintype "bidirectional"))
      (node (ref "X-NORTH") (pin "108") (pinfunction "108_108") (pintype "bidirectional"))
      (node (ref "X-NORTH") (pin "114") (pinfunction "114_114") (pintype "bidirectional"))
      (node (ref "X-NORTH") (pin "12") (pinfunction "12_12") (pintype "bidirectional"))
      (node (ref "X-NORTH") (pin "120") (pinfunction "120_120") (pintype "bidirectional"))
      (node (ref "X-NORTH") (pin "126") (pinfunction "126_126") (pintype "bidirectional"))
      (node (ref "X-NORTH") (pin "132") (pinfunction "132_132") (pintype "bidirectional"))
      (node (ref "X-NORTH") (pin "138") (pinfunction "138_138") (pintype "bidirectional"))
      (node (ref "X-NORTH") (pin "139") (pinfunction "139_139") (pintype "bidirectional"))
      (node (ref "X-NORTH") (pin "18") (pinfunction "18_18") (pintype "bidirectional"))
      (node (ref "X-NORTH") (pin "24") (pinfunction "24_24") (pintype "bidirectional"))
      (node (ref "X-NORTH") (pin "30") (pinfunction "30_30") (pintype "bidirectional"))
      (node (ref "X-NORTH") (pin "36") (pinfunction "36_36") (pintype "bidirectional"))
      (node (ref "X-NORTH") (pin "42") (pinfunction "42_42") (pintype "bidirectional"))
      (node (ref "X-NORTH") (pin "43") (pinfunction "43_43") (pintype "bidirectional"))
      (node (ref "X-NORTH") (pin "48") (pinfunction "48_48") (pintype "bidirectional"))
      (node (ref "X-NORTH") (pin "54") (pinfunction "54_54") (pintype "bidirectional"))
      (node (ref "X-NORTH") (pin "60") (pinfunction "60_60") (pintype "bidirectional"))
      (node (ref "X-NORTH") (pin "66") (pinfunction "66_66") (pintype "bidirectional"))
      (node (ref "X-NORTH") (pin "72") (pinfunction "72_72") (pintype "bidirectional"))
      (node (ref "X-NORTH") (pin "78") (pinfunction "78_78") (pintype "bidirectional"))
      (node (ref "X-NORTH") (pin "84") (pinfunction "84_84") (pintype "bidirectional"))
      (node (ref "X-NORTH") (pin "90") (pinfunction "90_90") (pintype "bidirectional"))
      (node (ref "X-NORTH") (pin "96") (pinfunction "96_96") (pintype "bidirectional"))
      (node (ref "X-SOUTH") (pin "102") (pinfunction "102_102") (pintype "bidirectional"))
      (node (ref "X-SOUTH") (pin "103") (pinfunction "103_103") (pintype "bidirectional"))
      (node (ref "X-SOUTH") (pin "108") (pinfunction "108_108") (pintype "bidirectional"))
      (node (ref "X-SOUTH") (pin "114") (pinfunction "114_114") (pintype "bidirectional"))
      (node (ref "X-SOUTH") (pin "12") (pinfunction "12_12") (pintype "bidirectional"))
      (node (ref "X-SOUTH") (pin "120") (pinfunction "120_120") (pintype "bidirectional"))
      (node (ref "X-SOUTH") (pin "126") (pinfunction "126_126") (pintype "bidirectional"))
      (node (ref "X-SOUTH") (pin "132") (pinfunction "132_132") (pintype "bidirectional"))
      (node (ref "X-SOUTH") (pin "138") (pinfunction "138_138") (pintype "bidirectional"))
      (node (ref "X-SOUTH") (pin "139") (pinfunction "139_139") (pintype "bidirectional"))
      (node (ref "X-SOUTH") (pin "18") (pinfunction "18_18") (pintype "bidirectional"))
      (node (ref "X-SOUTH") (pin "24") (pinfunction "24_24") (pintype "bidirectional"))
      (node (ref "X-SOUTH") (pin "30") (pinfunction "30_30") (pintype "bidirectional"))
      (node (ref "X-SOUTH") (pin "36") (pinfunction "36_36") (pintype "bidirectional"))
      (node (ref "X-SOUTH") (pin "42") (pinfunction "42_42") (pintype "bidirectional"))
      (node (ref "X-SOUTH") (pin "43") (pinfunction "43_43") (pintype "bidirectional"))
      (node (ref "X-SOUTH") (pin "48") (pinfunction "48_48") (pintype "bidirectional"))
      (node (ref "X-SOUTH") (pin "54") (pinfunction "54_54") (pintype "bidirectional"))
      (node (ref "X-SOUTH") (pin "60") (pinfunction "60_60") (pintype "bidirectional"))
      (node (ref "X-SOUTH") (pin "66") (pinfunction "66_66") (pintype "bidirectional"))
      (node (ref "X-SOUTH") (pin "72") (pinfunction "72_72") (pintype "bidirectional"))
      (node (ref "X-SOUTH") (pin "78") (pinfunction "78_78") (pintype "bidirectional"))
      (node (ref "X-SOUTH") (pin "84") (pinfunction "84_84") (pintype "bidirectional"))
      (node (ref "X-SOUTH") (pin "90") (pinfunction "90_90") (pintype "bidirectional"))
      (node (ref "X-SOUTH") (pin "96") (pinfunction "96_96") (pintype "bidirectional"))
    )
    (net (code "4") (name "N$38") (class "Default")
      (node (ref "SENSOR") (pin "F4") (pinfunction "DIO1_F4") (pintype "output"))
    )
    (net (code "5") (name "N$39") (class "Default")
      (node (ref "SENSOR") (pin "E4") (pinfunction "DIO2_E4") (pintype "output"))
    )
    (net (code "6") (name "N$40") (class "Default")
      (node (ref "SENSOR") (pin "H4") (pinfunction "DIO3_H4") (pintype "output"))
    )
    (net (code "7") (name "N$41") (class "Default")
      (node (ref "SENSOR") (pin "G3") (pinfunction "DIO4_G3") (pintype "output"))
    )
    (net (code "8") (name "N$42") (class "Default")
      (node (ref "SENSOR") (pin "A2") (pinfunction "TANA_A2") (pintype "output"))
    )
    (net (code "9") (name "N00_N") (class "Default")
      (node (ref "R25") (pin "2") (pinfunction "2_2") (pintype "passive"))
      (node (ref "SENSOR") (pin "E6") (pinfunction "LVDS_CLK_P_E6") (pintype "input"))
      (node (ref "X-NORTH") (pin "16") (pinfunction "16_16") (pintype "bidirectional"))
    )
    (net (code "10") (name "N00_P") (class "Default")
      (node (ref "R25") (pin "1") (pinfunction "1_1") (pintype "passive"))
      (node (ref "SENSOR") (pin "E5") (pinfunction "LVDS_CLK_N_E5") (pintype "input"))
      (node (ref "X-NORTH") (pin "14") (pinfunction "14_14") (pintype "bidirectional"))
    )
    (net (code "11") (name "N01_N") (class "Default")
      (node (ref "SENSOR") (pin "G7") (pinfunction "OUTCLK_P_G7") (pintype "output"))
      (node (ref "X-NORTH") (pin "17") (pinfunction "17_17") (pintype "bidirectional"))
    )
    (net (code "12") (name "N01_P") (class "Default")
      (node (ref "SENSOR") (pin "G6") (pinfunction "OUTCLK_N_G6") (pintype "output"))
      (node (ref "X-NORTH") (pin "15") (pinfunction "15_15") (pintype "bidirectional"))
    )
    (net (code "13") (name "N02_N") (class "Default")
      (node (ref "SENSOR") (pin "F7") (pinfunction "OUT33_P_F7") (pintype "output"))
      (node (ref "X-NORTH") (pin "22") (pinfunction "22_22") (pintype "bidirectional"))
    )
    (net (code "14") (name "N02_P") (class "Default")
      (node (ref "SENSOR") (pin "F6") (pinfunction "OUT33_N_F6") (pintype "output"))
      (node (ref "X-NORTH") (pin "20") (pinfunction "20_20") (pintype "bidirectional"))
    )
    (net (code "15") (name "N03_N") (class "Default")
      (node (ref "X-NORTH") (pin "23") (pinfunction "23_23") (pintype "bidirectional"))
    )
    (net (code "16") (name "N03_P") (class "Default")
      (node (ref "X-NORTH") (pin "21") (pinfunction "21_21") (pintype "bidirectional"))
    )
    (net (code "17") (name "N04_N") (class "Default")
      (node (ref "SENSOR") (pin "E8") (pinfunction "OUT35_P_E8") (pintype "output"))
      (node (ref "X-NORTH") (pin "28") (pinfunction "28_28") (pintype "bidirectional"))
    )
    (net (code "18") (name "N04_P") (class "Default")
      (node (ref "SENSOR") (pin "E7") (pinfunction "OUT35_N_E7") (pintype "output"))
      (node (ref "X-NORTH") (pin "26") (pinfunction "26_26") (pintype "bidirectional"))
    )
    (net (code "19") (name "N05_N") (class "Default")
      (node (ref "SENSOR") (pin "H8") (pinfunction "OUT34_P_H8") (pintype "output"))
      (node (ref "X-NORTH") (pin "29") (pinfunction "29_29") (pintype "bidirectional"))
    )
    (net (code "20") (name "N05_P") (class "Default")
      (node (ref "SENSOR") (pin "H7") (pinfunction "OUT34_N_H7") (pintype "output"))
      (node (ref "X-NORTH") (pin "27") (pinfunction "27_27") (pintype "bidirectional"))
    )
    (net (code "21") (name "N06_N") (class "Default")
      (node (ref "SENSOR") (pin "F9") (pinfunction "OUT37_P_F9") (pintype "output"))
      (node (ref "X-NORTH") (pin "34") (pinfunction "34_34") (pintype "bidirectional"))
    )
    (net (code "22") (name "N06_P") (class "Default")
      (node (ref "SENSOR") (pin "F8") (pinfunction "OUT37_N_F8") (pintype "output"))
      (node (ref "X-NORTH") (pin "32") (pinfunction "32_32") (pintype "bidirectional"))
    )
    (net (code "23") (name "N07_N") (class "Default")
      (node (ref "SENSOR") (pin "G9") (pinfunction "OUT36_P_G9") (pintype "output"))
      (node (ref "X-NORTH") (pin "35") (pinfunction "35_35") (pintype "bidirectional"))
    )
    (net (code "24") (name "N07_P") (class "Default")
      (node (ref "SENSOR") (pin "G8") (pinfunction "OUT36_N_G8") (pintype "output"))
      (node (ref "X-NORTH") (pin "33") (pinfunction "33_33") (pintype "bidirectional"))
    )
    (net (code "25") (name "N08_N") (class "Default")
      (node (ref "SENSOR") (pin "E10") (pinfunction "OUT38_P_E10") (pintype "output"))
      (node (ref "X-NORTH") (pin "40") (pinfunction "40_40") (pintype "bidirectional"))
    )
    (net (code "26") (name "N08_P") (class "Default")
      (node (ref "SENSOR") (pin "E9") (pinfunction "OUT38_N_E9") (pintype "output"))
      (node (ref "X-NORTH") (pin "38") (pinfunction "38_38") (pintype "bidirectional"))
    )
    (net (code "27") (name "N09_N") (class "Default")
      (node (ref "SENSOR") (pin "G11") (pinfunction "OUT39_P_G11") (pintype "output"))
      (node (ref "X-NORTH") (pin "41") (pinfunction "41_41") (pintype "bidirectional"))
    )
    (net (code "28") (name "N09_P") (class "Default")
      (node (ref "SENSOR") (pin "G10") (pinfunction "OUT39_N_G10") (pintype "output"))
      (node (ref "X-NORTH") (pin "39") (pinfunction "39_39") (pintype "bidirectional"))
    )
    (net (code "29") (name "N10_N") (class "Default")
      (node (ref "SENSOR") (pin "F11") (pinfunction "OUT40_P_F11") (pintype "output"))
      (node (ref "X-NORTH") (pin "46") (pinfunction "46_46") (pintype "bidirectional"))
    )
    (net (code "30") (name "N10_P") (class "Default")
      (node (ref "SENSOR") (pin "F10") (pinfunction "OUT40_N_F10") (pintype "output"))
      (node (ref "X-NORTH") (pin "44") (pinfunction "44_44") (pintype "bidirectional"))
    )
    (net (code "31") (name "N11_N") (class "Default")
      (node (ref "SENSOR") (pin "H12") (pinfunction "OUT41_P_H12") (pintype "output"))
      (node (ref "X-NORTH") (pin "47") (pinfunction "47_47") (pintype "bidirectional"))
    )
    (net (code "32") (name "N11_P") (class "Default")
      (node (ref "SENSOR") (pin "H11") (pinfunction "OUT41_N_H11") (pintype "output"))
      (node (ref "X-NORTH") (pin "45") (pinfunction "45_45") (pintype "bidirectional"))
    )
    (net (code "33") (name "N12_N") (class "Default")
      (node (ref "SENSOR") (pin "E12") (pinfunction "OUT42_P_E12") (pintype "output"))
      (node (ref "X-NORTH") (pin "52") (pinfunction "52_52") (pintype "bidirectional"))
    )
    (net (code "34") (name "N12_P") (class "Default")
      (node (ref "SENSOR") (pin "E11") (pinfunction "OUT42_N_E11") (pintype "output"))
      (node (ref "X-NORTH") (pin "50") (pinfunction "50_50") (pintype "bidirectional"))
    )
    (net (code "35") (name "N13_N") (class "Default")
      (node (ref "SENSOR") (pin "G13") (pinfunction "OUT43_P_G13") (pintype "output"))
      (node (ref "X-NORTH") (pin "53") (pinfunction "53_53") (pintype "bidirectional"))
    )
    (net (code "36") (name "N13_P") (class "Default")
      (node (ref "SENSOR") (pin "G12") (pinfunction "OUT43_N_G12") (pintype "output"))
      (node (ref "X-NORTH") (pin "51") (pinfunction "51_51") (pintype "bidirectional"))
    )
    (net (code "37") (name "N14_N") (class "Default")
      (node (ref "SENSOR") (pin "F13") (pinfunction "OUT44_P_F13") (pintype "output"))
      (node (ref "X-NORTH") (pin "58") (pinfunction "58_58") (pintype "bidirectional"))
    )
    (net (code "38") (name "N14_P") (class "Default")
      (node (ref "SENSOR") (pin "F12") (pinfunction "OUT44_N_F12") (pintype "output"))
      (node (ref "X-NORTH") (pin "56") (pinfunction "56_56") (pintype "bidirectional"))
    )
    (net (code "39") (name "N15_N") (class "Default")
      (node (ref "SENSOR") (pin "H14") (pinfunction "OUT45_P_H14") (pintype "output"))
      (node (ref "X-NORTH") (pin "59") (pinfunction "59_59") (pintype "bidirectional"))
    )
    (net (code "40") (name "N15_P") (class "Default")
      (node (ref "SENSOR") (pin "H13") (pinfunction "OUT45_N_H13") (pintype "output"))
      (node (ref "X-NORTH") (pin "57") (pinfunction "57_57") (pintype "bidirectional"))
    )
    (net (code "41") (name "N16_N") (class "Default")
      (node (ref "SENSOR") (pin "E14") (pinfunction "OUT46_P_E14") (pintype "output"))
      (node (ref "X-NORTH") (pin "64") (pinfunction "64_64") (pintype "bidirectional"))
    )
    (net (code "42") (name "N16_P") (class "Default")
      (node (ref "SENSOR") (pin "E13") (pinfunction "OUT46_N_E13") (pintype "output"))
      (node (ref "X-NORTH") (pin "62") (pinfunction "62_62") (pintype "bidirectional"))
    )
    (net (code "43") (name "N17_N") (class "Default")
      (node (ref "SENSOR") (pin "G15") (pinfunction "OUT47_P_G15") (pintype "output"))
      (node (ref "X-NORTH") (pin "65") (pinfunction "65_65") (pintype "bidirectional"))
    )
    (net (code "44") (name "N17_P") (class "Default")
      (node (ref "SENSOR") (pin "G14") (pinfunction "OUT47_N_G14") (pintype "output"))
      (node (ref "X-NORTH") (pin "63") (pinfunction "63_63") (pintype "bidirectional"))
    )
    (net (code "45") (name "N18_N") (class "Default")
      (node (ref "SENSOR") (pin "F15") (pinfunction "OUT48_P_F15") (pintype "output"))
      (node (ref "X-NORTH") (pin "70") (pinfunction "70_70") (pintype "bidirectional"))
    )
    (net (code "46") (name "N18_P") (class "Default")
      (node (ref "SENSOR") (pin "F14") (pinfunction "OUT48_N_F14") (pintype "output"))
      (node (ref "X-NORTH") (pin "68") (pinfunction "68_68") (pintype "bidirectional"))
    )
    (net (code "47") (name "N19_N") (class "Default")
      (node (ref "SENSOR") (pin "G17") (pinfunction "OUT50_P_G17") (pintype "output"))
      (node (ref "X-NORTH") (pin "71") (pinfunction "71_71") (pintype "bidirectional"))
    )
    (net (code "48") (name "N19_P") (class "Default")
      (node (ref "SENSOR") (pin "G16") (pinfunction "OUT50_N_G16") (pintype "output"))
      (node (ref "X-NORTH") (pin "69") (pinfunction "69_69") (pintype "bidirectional"))
    )
    (net (code "49") (name "N20_N") (class "Default")
      (node (ref "SENSOR") (pin "F17") (pinfunction "OUT49_P_F17") (pintype "output"))
      (node (ref "X-NORTH") (pin "76") (pinfunction "76_76") (pintype "bidirectional"))
    )
    (net (code "50") (name "N20_P") (class "Default")
      (node (ref "SENSOR") (pin "F16") (pinfunction "OUT49_N_F16") (pintype "output"))
      (node (ref "X-NORTH") (pin "74") (pinfunction "74_74") (pintype "bidirectional"))
    )
    (net (code "51") (name "N21_N") (class "Default")
      (node (ref "SENSOR") (pin "H18") (pinfunction "OUT52_P_H18") (pintype "output"))
      (node (ref "X-NORTH") (pin "77") (pinfunction "77_77") (pintype "bidirectional"))
    )
    (net (code "52") (name "N21_P") (class "Default")
      (node (ref "SENSOR") (pin "H17") (pinfunction "OUT52_N_H17") (pintype "output"))
      (node (ref "X-NORTH") (pin "75") (pinfunction "75_75") (pintype "bidirectional"))
    )
    (net (code "53") (name "N22_N") (class "Default")
      (node (ref "SENSOR") (pin "E18") (pinfunction "OUT51_P_E18") (pintype "output"))
      (node (ref "X-NORTH") (pin "82") (pinfunction "82_82") (pintype "bidirectional"))
    )
    (net (code "54") (name "N22_P") (class "Default")
      (node (ref "SENSOR") (pin "E17") (pinfunction "OUT51_N_E17") (pintype "output"))
      (node (ref "X-NORTH") (pin "80") (pinfunction "80_80") (pintype "bidirectional"))
    )
    (net (code "55") (name "N23_N") (class "Default")
      (node (ref "SENSOR") (pin "G19") (pinfunction "OUT54_P_G19") (pintype "output"))
      (node (ref "X-NORTH") (pin "83") (pinfunction "83_83") (pintype "bidirectional"))
    )
    (net (code "56") (name "N23_P") (class "Default")
      (node (ref "SENSOR") (pin "G18") (pinfunction "OUT54_N_G18") (pintype "output"))
      (node (ref "X-NORTH") (pin "81") (pinfunction "81_81") (pintype "bidirectional"))
    )
    (net (code "57") (name "N24_N") (class "Default")
      (node (ref "SENSOR") (pin "F19") (pinfunction "OUT53_P_F19") (pintype "output"))
      (node (ref "X-NORTH") (pin "88") (pinfunction "88_88") (pintype "bidirectional"))
    )
    (net (code "58") (name "N24_P") (class "Default")
      (node (ref "SENSOR") (pin "F18") (pinfunction "OUT53_N_F18") (pintype "output"))
      (node (ref "X-NORTH") (pin "86") (pinfunction "86_86") (pintype "bidirectional"))
    )
    (net (code "59") (name "N25_N") (class "Default")
      (node (ref "SENSOR") (pin "H20") (pinfunction "OUT56_P_H20") (pintype "output"))
      (node (ref "X-NORTH") (pin "89") (pinfunction "89_89") (pintype "bidirectional"))
    )
    (net (code "60") (name "N25_P") (class "Default")
      (node (ref "SENSOR") (pin "H19") (pinfunction "OUT56_N_H19") (pintype "output"))
      (node (ref "X-NORTH") (pin "87") (pinfunction "87_87") (pintype "bidirectional"))
    )
    (net (code "61") (name "N26_N") (class "Default")
      (node (ref "SENSOR") (pin "E20") (pinfunction "OUT55_P_E20") (pintype "output"))
      (node (ref "X-NORTH") (pin "94") (pinfunction "94_94") (pintype "bidirectional"))
    )
    (net (code "62") (name "N26_P") (class "Default")
      (node (ref "SENSOR") (pin "E19") (pinfunction "OUT55_N_E19") (pintype "output"))
      (node (ref "X-NORTH") (pin "92") (pinfunction "92_92") (pintype "bidirectional"))
    )
    (net (code "63") (name "N27_N") (class "Default")
      (node (ref "SENSOR") (pin "G21") (pinfunction "OUT58_P_G21") (pintype "output"))
      (node (ref "X-NORTH") (pin "95") (pinfunction "95_95") (pintype "bidirectional"))
    )
    (net (code "64") (name "N27_P") (class "Default")
      (node (ref "SENSOR") (pin "G20") (pinfunction "OUT58_N_G20") (pintype "output"))
      (node (ref "X-NORTH") (pin "93") (pinfunction "93_93") (pintype "bidirectional"))
    )
    (net (code "65") (name "N28_N") (class "Default")
      (node (ref "SENSOR") (pin "F21") (pinfunction "OUT57_P_F21") (pintype "output"))
      (node (ref "X-NORTH") (pin "100") (pinfunction "100_100") (pintype "bidirectional"))
    )
    (net (code "66") (name "N28_P") (class "Default")
      (node (ref "SENSOR") (pin "F20") (pinfunction "OUT57_N_F20") (pintype "output"))
      (node (ref "X-NORTH") (pin "98") (pinfunction "98_98") (pintype "bidirectional"))
    )
    (net (code "67") (name "N29_N") (class "Default")
      (node (ref "SENSOR") (pin "G23") (pinfunction "OUT61_P_G23") (pintype "output"))
      (node (ref "X-NORTH") (pin "101") (pinfunction "101_101") (pintype "bidirectional"))
    )
    (net (code "68") (name "N29_P") (class "Default")
      (node (ref "SENSOR") (pin "G22") (pinfunction "OUT61_N_G22") (pintype "output"))
      (node (ref "X-NORTH") (pin "99") (pinfunction "99_99") (pintype "bidirectional"))
    )
    (net (code "69") (name "N30_N") (class "Default")
      (node (ref "SENSOR") (pin "E22") (pinfunction "OUT59_P_E22") (pintype "output"))
      (node (ref "X-NORTH") (pin "106") (pinfunction "106_106") (pintype "bidirectional"))
    )
    (net (code "70") (name "N30_P") (class "Default")
      (node (ref "SENSOR") (pin "E21") (pinfunction "OUT59_N_E21") (pintype "output"))
      (node (ref "X-NORTH") (pin "104") (pinfunction "104_104") (pintype "bidirectional"))
    )
    (net (code "71") (name "N31_N") (class "Default")
      (node (ref "SENSOR") (pin "H24") (pinfunction "OUT63_P_H24") (pintype "output"))
      (node (ref "X-NORTH") (pin "107") (pinfunction "107_107") (pintype "bidirectional"))
    )
    (net (code "72") (name "N31_P") (class "Default")
      (node (ref "SENSOR") (pin "H23") (pinfunction "OUT63_N_H23") (pintype "output"))
      (node (ref "X-NORTH") (pin "105") (pinfunction "105_105") (pintype "bidirectional"))
    )
    (net (code "73") (name "N32_N") (class "Default")
      (node (ref "SENSOR") (pin "F23") (pinfunction "OUT60_P_F23") (pintype "output"))
      (node (ref "X-NORTH") (pin "112") (pinfunction "112_112") (pintype "bidirectional"))
    )
    (net (code "74") (name "N32_P") (class "Default")
      (node (ref "SENSOR") (pin "F22") (pinfunction "OUT60_N_F22") (pintype "output"))
      (node (ref "X-NORTH") (pin "110") (pinfunction "110_110") (pintype "bidirectional"))
    )
    (net (code "75") (name "N33_N") (class "Default")
      (node (ref "SENSOR") (pin "G25") (pinfunction "OUT64_P_G25") (pintype "output"))
      (node (ref "X-NORTH") (pin "113") (pinfunction "113_113") (pintype "bidirectional"))
    )
    (net (code "76") (name "N33_P") (class "Default")
      (node (ref "SENSOR") (pin "G24") (pinfunction "OUT64_N_G24") (pintype "output"))
      (node (ref "X-NORTH") (pin "111") (pinfunction "111_111") (pintype "bidirectional"))
    )
    (net (code "77") (name "N34_N") (class "Default")
      (node (ref "SENSOR") (pin "E24") (pinfunction "OUT62_P_E24") (pintype "output"))
      (node (ref "X-NORTH") (pin "118") (pinfunction "118_118") (pintype "bidirectional"))
    )
    (net (code "78") (name "N34_P") (class "Default")
      (node (ref "SENSOR") (pin "E23") (pinfunction "OUT62_N_E23") (pintype "output"))
      (node (ref "X-NORTH") (pin "116") (pinfunction "116_116") (pintype "bidirectional"))
    )
    (net (code "79") (name "N35_N") (class "Default")
      (node (ref "U6") (pin "4") (pinfunction "A4_4") (pintype "bidirectional"))
      (node (ref "X-NORTH") (pin "119") (pinfunction "119_119") (pintype "bidirectional"))
    )
    (net (code "80") (name "N35_P") (class "Default")
      (node (ref "U6") (pin "3") (pinfunction "A3_3") (pintype "bidirectional"))
      (node (ref "X-NORTH") (pin "117") (pinfunction "117_117") (pintype "bidirectional"))
    )
    (net (code "81") (name "N36_N") (class "Default")
      (node (ref "X-NORTH") (pin "124") (pinfunction "124_124") (pintype "bidirectional"))
    )
    (net (code "82") (name "N36_P") (class "Default")
      (node (ref "X-NORTH") (pin "122") (pinfunction "122_122") (pintype "bidirectional"))
    )
    (net (code "83") (name "N37_N") (class "Default")
      (node (ref "U5") (pin "3") (pinfunction "A3_3") (pintype "bidirectional"))
      (node (ref "X-NORTH") (pin "125") (pinfunction "125_125") (pintype "bidirectional"))
    )
    (net (code "84") (name "N37_P") (class "Default")
      (node (ref "U5") (pin "4") (pinfunction "A4_4") (pintype "bidirectional"))
      (node (ref "X-NORTH") (pin "123") (pinfunction "123_123") (pintype "bidirectional"))
    )
    (net (code "85") (name "N38_N") (class "Default")
      (node (ref "U6") (pin "2") (pinfunction "A2_2") (pintype "bidirectional"))
      (node (ref "X-NORTH") (pin "130") (pinfunction "130_130") (pintype "bidirectional"))
    )
    (net (code "86") (name "N38_P") (class "Default")
      (node (ref "U6") (pin "1") (pinfunction "A1_1") (pintype "bidirectional"))
      (node (ref "X-NORTH") (pin "128") (pinfunction "128_128") (pintype "bidirectional"))
    )
    (net (code "87") (name "N39_N") (class "Default")
      (node (ref "U5") (pin "1") (pinfunction "A1_1") (pintype "bidirectional"))
      (node (ref "X-NORTH") (pin "131") (pinfunction "131_131") (pintype "bidirectional"))
    )
    (net (code "88") (name "N39_P") (class "Default")
      (node (ref "U5") (pin "2") (pinfunction "A2_2") (pintype "bidirectional"))
      (node (ref "X-NORTH") (pin "129") (pinfunction "129_129") (pintype "bidirectional"))
    )
    (net (code "89") (name "N_CHK_V") (class "Default")
      (node (ref "C2") (pin "1") (pinfunction "1_1") (pintype "passive"))
      (node (ref "C3") (pin "1") (pinfunction "1_1") (pintype "passive"))
      (node (ref "C4") (pin "1") (pinfunction "1_1") (pintype "passive"))
      (node (ref "R19") (pin "1") (pinfunction "1_1") (pintype "passive"))
      (node (ref "TP1") (pin "TP") (pinfunction "TP_TP") (pintype "input"))
      (node (ref "UNE") (pin "8") (pinfunction "VDD_8") (pintype "power_in"))
      (node (ref "UNN") (pin "8") (pinfunction "VDD_8") (pintype "power_in"))
      (node (ref "UNW") (pin "8") (pinfunction "VDD_8") (pintype "power_in"))
      (node (ref "X-NORTH") (pin "10") (pinfunction "10_10") (pintype "bidirectional"))
      (node (ref "X-NORTH") (pin "8") (pinfunction "8_8") (pintype "bidirectional"))
    )
    (net (code "90") (name "N_I2C_V") (class "Default")
      (node (ref "C1") (pin "1") (pinfunction "1_1") (pintype "passive"))
      (node (ref "R1X") (pin "1") (pinfunction "1_1") (pintype "passive"))
      (node (ref "UEP") (pin "8") (pinfunction "VCC_8") (pintype "power_in"))
      (node (ref "X-NORTH") (pin "135") (pinfunction "135_135") (pintype "bidirectional"))
      (node (ref "X-NORTH") (pin "137") (pinfunction "137_137") (pintype "bidirectional"))
    )
    (net (code "91") (name "N_REF") (class "Default")
      (node (ref "R19") (pin "2") (pinfunction "2_2") (pintype "passive"))
      (node (ref "TP2") (pin "TP") (pinfunction "TP_TP") (pintype "input"))
      (node (ref "U1") (pin "3") (pinfunction "CATHODE_3") (pintype "output"))
      (node (ref "U1") (pin "4") (pinfunction "REF_4") (pintype "input"))
      (node (ref "UNE") (pin "2") (pinfunction "VINA-_2") (pintype "input"))
      (node (ref "UNE") (pin "5") (pinfunction "VINB+_5") (pintype "input"))
      (node (ref "UNN") (pin "2") (pinfunction "VINA-_2") (pintype "input"))
      (node (ref "UNN") (pin "5") (pinfunction "VINB+_5") (pintype "input"))
      (node (ref "UNW") (pin "2") (pinfunction "VINA-_2") (pintype "input"))
      (node (ref "UNW") (pin "5") (pinfunction "VINB+_5") (pintype "input"))
    )
    (net (code "92") (name "N_SCK") (class "Default")
      (node (ref "U4") (pin "15") (pinfunction "1B1_15") (pintype "output"))
      (node (ref "X-NORTH") (pin "144") (pinfunction "144_144") (pintype "bidirectional"))
    )
    (net (code "93") (name "N_SCL") (class "Default")
      (node (ref "UEP") (pin "6") (pinfunction "SCL_6") (pintype "input"))
      (node (ref "X-NORTH") (pin "143") (pinfunction "143_143") (pintype "bidirectional"))
    )
    (net (code "94") (name "N_SDA") (class "Default")
      (node (ref "UEP") (pin "5") (pinfunction "SDA_5") (pintype "bidirectional"))
      (node (ref "X-NORTH") (pin "141") (pinfunction "141_141") (pintype "bidirectional"))
    )
    (net (code "95") (name "N_SDI") (class "Default")
      (node (ref "U4") (pin "13") (pinfunction "2B1_13") (pintype "output"))
      (node (ref "X-NORTH") (pin "140") (pinfunction "140_140") (pintype "bidirectional"))
    )
    (net (code "96") (name "N_SDO") (class "Default")
      (node (ref "U4") (pin "14") (pinfunction "1B2_14") (pintype "output"))
      (node (ref "X-NORTH") (pin "142") (pinfunction "142_142") (pintype "bidirectional"))
    )
    (net (code "97") (name "N_SPI_V") (class "Default")
      (node (ref "C71") (pin "1") (pinfunction "1_1") (pintype "passive"))
      (node (ref "U4") (pin "2") (pinfunction "VCCB_2") (pintype "power_in"))
      (node (ref "X-NORTH") (pin "134") (pinfunction "134_134") (pintype "bidirectional"))
      (node (ref "X-NORTH") (pin "136") (pinfunction "136_136") (pintype "bidirectional"))
    )
    (net (code "98") (name "N_VE") (class "Default")
      (node (ref "C50") (pin "1") (pinfunction "1_1") (pintype "passive"))
      (node (ref "C51") (pin "1") (pinfunction "1_1") (pintype "passive"))
      (node (ref "C52") (pin "1") (pinfunction "1_1") (pintype "passive"))
      (node (ref "C53") (pin "1") (pinfunction "1_1") (pintype "passive"))
      (node (ref "C54") (pin "1") (pinfunction "1_1") (pintype "passive"))
      (node (ref "C55") (pin "1") (pinfunction "1_1") (pintype "passive"))
      (node (ref "C56") (pin "1") (pinfunction "1_1") (pintype "passive"))
      (node (ref "C67") (pin "1") (pinfunction "1_1") (pintype "passive"))
      (node (ref "C69") (pin "1") (pinfunction "1_1") (pintype "passive"))
      (node (ref "C75") (pin "1") (pinfunction "1_1") (pintype "passive"))
      (node (ref "C76") (pin "1") (pinfunction "1_1") (pintype "passive"))
      (node (ref "C77") (pin "1") (pinfunction "1_1") (pintype "passive"))
      (node (ref "C84") (pin "1") (pinfunction "1_1") (pintype "passive"))
      (node (ref "C85") (pin "1") (pinfunction "1_1") (pintype "passive"))
      (node (ref "C86") (pin "1") (pinfunction "1_1") (pintype "passive"))
      (node (ref "SENSOR") (pin "C26") (pinfunction "VDD33_C26") (pintype "power_in"))
      (node (ref "SENSOR") (pin "C27") (pinfunction "VDD33_C27") (pintype "power_in"))
      (node (ref "SENSOR") (pin "D26") (pinfunction "VDD33_D26") (pintype "power_in"))
      (node (ref "SENSOR") (pin "D3") (pinfunction "VDD33_D3") (pintype "power_in"))
      (node (ref "SENSOR") (pin "E26") (pinfunction "VDD33_E26") (pintype "power_in"))
      (node (ref "SENSOR") (pin "F26") (pinfunction "VDD33_F26") (pintype "power_in"))
      (node (ref "SENSOR") (pin "F5") (pinfunction "VDD33_F5") (pintype "power_in"))
      (node (ref "TP7") (pin "TP") (pinfunction "TP_TP") (pintype "input"))
      (node (ref "U4") (pin "3") (pinfunction "VCCA_3") (pintype "power_in"))
      (node (ref "U4") (pin "5") (pinfunction "2DIR_5") (pintype "input"))
      (node (ref "U5") (pin "13") (pinfunction "VCCB_13") (pintype "power_in"))
      (node (ref "U6") (pin "13") (pinfunction "VCCB_13") (pintype "power_in"))
      (node (ref "X-NORTH") (pin "109") (pinfunction "109_109") (pintype "bidirectional"))
      (node (ref "X-NORTH") (pin "115") (pinfunction "115_115") (pintype "bidirectional"))
      (node (ref "X-NORTH") (pin "121") (pinfunction "121_121") (pintype "bidirectional"))
      (node (ref "X-NORTH") (pin "127") (pinfunction "127_127") (pintype "bidirectional"))
      (node (ref "X-NORTH") (pin "133") (pinfunction "133_133") (pintype "bidirectional"))
    )
    (net (code "99") (name "N_VE_CV") (class "Default")
      (node (ref "C10") (pin "1") (pinfunction "1_1") (pintype "passive"))
      (node (ref "R7") (pin "1") (pinfunction "1_1") (pintype "passive"))
      (node (ref "X-NORTH") (pin "6") (pinfunction "6_6") (pintype "bidirectional"))
    )
    (net (code "100") (name "N_VE_OV") (class "Default")
      (node (ref "UNE") (pin "7") (pinfunction "OUTB_7") (pintype "output"))
      (node (ref "X-NORTH") (pin "5") (pinfunction "5_5") (pintype "bidirectional"))
    )
    (net (code "101") (name "N_VE_UV") (class "Default")
      (node (ref "UNE") (pin "1") (pinfunction "OUTA_1") (pintype "output"))
      (node (ref "X-NORTH") (pin "11") (pinfunction "11_11") (pintype "bidirectional"))
    )
    (net (code "102") (name "N_VN") (class "Default")
      (node (ref "C31") (pin "1") (pinfunction "1_1") (pintype "passive"))
      (node (ref "C32") (pin "1") (pinfunction "1_1") (pintype "passive"))
      (node (ref "C33") (pin "1") (pinfunction "1_1") (pintype "passive"))
      (node (ref "C34") (pin "1") (pinfunction "1_1") (pintype "passive"))
      (node (ref "C35") (pin "1") (pinfunction "1_1") (pintype "passive"))
      (node (ref "C36") (pin "1") (pinfunction "1_1") (pintype "passive"))
      (node (ref "C37") (pin "1") (pinfunction "1_1") (pintype "passive"))
      (node (ref "C38") (pin "1") (pinfunction "1_1") (pintype "passive"))
      (node (ref "C39") (pin "1") (pinfunction "1_1") (pintype "passive"))
      (node (ref "C40") (pin "1") (pinfunction "1_1") (pintype "passive"))
      (node (ref "C41") (pin "1") (pinfunction "1_1") (pintype "passive"))
      (node (ref "C42") (pin "1") (pinfunction "1_1") (pintype "passive"))
      (node (ref "C43") (pin "1") (pinfunction "1_1") (pintype "passive"))
      (node (ref "C44") (pin "1") (pinfunction "1_1") (pintype "passive"))
      (node (ref "C68") (pin "1") (pinfunction "1_1") (pintype "passive"))
      (node (ref "C70") (pin "1") (pinfunction "1_1") (pintype "passive"))
      (node (ref "C78") (pin "1") (pinfunction "1_1") (pintype "passive"))
      (node (ref "C79") (pin "1") (pinfunction "1_1") (pintype "passive"))
      (node (ref "C80") (pin "1") (pinfunction "1_1") (pintype "passive"))
      (node (ref "C87") (pin "1") (pinfunction "1_1") (pintype "passive"))
      (node (ref "C88") (pin "1") (pinfunction "1_1") (pintype "passive"))
      (node (ref "C89") (pin "1") (pinfunction "1_1") (pintype "passive"))
      (node (ref "SENSOR") (pin "A10") (pinfunction "VDD18_A10") (pintype "power_in"))
      (node (ref "SENSOR") (pin "A15") (pinfunction "VDD18_A15") (pintype "power_in"))
      (node (ref "SENSOR") (pin "A16") (pinfunction "VDD18_A16") (pintype "power_in"))
      (node (ref "SENSOR") (pin "A22") (pinfunction "VDD18_A22") (pintype "power_in"))
      (node (ref "SENSOR") (pin "A26") (pinfunction "VDD18_A26") (pintype "power_in"))
      (node (ref "SENSOR") (pin "A27") (pinfunction "VDD18_A27") (pintype "power_in"))
      (node (ref "SENSOR") (pin "B4") (pinfunction "VDD18_B4") (pintype "power_in"))
      (node (ref "SENSOR") (pin "E1") (pinfunction "VDD18_PLL_E1") (pintype "power_in"))
      (node (ref "SENSOR") (pin "H10") (pinfunction "VDD18_H10") (pintype "power_in"))
      (node (ref "SENSOR") (pin "H15") (pinfunction "VDD18_H15") (pintype "power_in"))
      (node (ref "SENSOR") (pin "H16") (pinfunction "VDD18_H16") (pintype "power_in"))
      (node (ref "SENSOR") (pin "H22") (pinfunction "VDD18_H22") (pintype "power_in"))
      (node (ref "SENSOR") (pin "H26") (pinfunction "VDD18_H26") (pintype "power_in"))
      (node (ref "SENSOR") (pin "H5") (pinfunction "VDD18_H5") (pintype "power_in"))
      (node (ref "TP5") (pin "TP") (pinfunction "TP_TP") (pintype "input"))
      (node (ref "U5") (pin "14") (pinfunction "VCCA_14") (pintype "power_in"))
      (node (ref "U5") (pin "15") (pinfunction "DIR1_15") (pintype "input"))
      (node (ref "U5") (pin "16") (pinfunction "DIR2_16") (pintype "input"))
      (node (ref "U5") (pin "5") (pinfunction "DIR3_5") (pintype "input"))
      (node (ref "U6") (pin "14") (pinfunction "VCCA_14") (pintype "power_in"))
      (node (ref "U6") (pin "16") (pinfunction "DIR2_16") (pintype "input"))
      (node (ref "X-NORTH") (pin "49") (pinfunction "49_49") (pintype "bidirectional"))
      (node (ref "X-NORTH") (pin "55") (pinfunction "55_55") (pintype "bidirectional"))
      (node (ref "X-NORTH") (pin "61") (pinfunction "61_61") (pintype "bidirectional"))
      (node (ref "X-NORTH") (pin "67") (pinfunction "67_67") (pintype "bidirectional"))
      (node (ref "X-NORTH") (pin "73") (pinfunction "73_73") (pintype "bidirectional"))
      (node (ref "X-NORTH") (pin "79") (pinfunction "79_79") (pintype "bidirectional"))
      (node (ref "X-NORTH") (pin "85") (pinfunction "85_85") (pintype "bidirectional"))
      (node (ref "X-NORTH") (pin "91") (pinfunction "91_91") (pintype "bidirectional"))
      (node (ref "X-NORTH") (pin "97") (pinfunction "97_97") (pintype "bidirectional"))
    )
    (net (code "103") (name "N_VN_CV") (class "Default")
      (node (ref "C9") (pin "1") (pinfunction "1_1") (pintype "passive"))
      (node (ref "R4") (pin "1") (pinfunction "1_1") (pintype "passive"))
      (node (ref "X-NORTH") (pin "4") (pinfunction "4_4") (pintype "bidirectional"))
    )
    (net (code "104") (name "N_VN_OV") (class "Default")
      (node (ref "UNN") (pin "7") (pinfunction "OUTB_7") (pintype "output"))
      (node (ref "X-NORTH") (pin "3") (pinfunction "3_3") (pintype "bidirectional"))
    )
    (net (code "105") (name "N_VN_UV") (class "Default")
      (node (ref "UNN") (pin "1") (pinfunction "OUTA_1") (pintype "output"))
      (node (ref "X-NORTH") (pin "9") (pinfunction "9_9") (pintype "bidirectional"))
    )
    (net (code "106") (name "N_VW") (class "Default")
      (node (ref "C57") (pin "1") (pinfunction "1_1") (pintype "passive"))
      (node (ref "C58") (pin "1") (pinfunction "1_1") (pintype "passive"))
      (node (ref "C59") (pin "1") (pinfunction "1_1") (pintype "passive"))
      (node (ref "SENSOR") (pin "E2") (pinfunction "VDD_RES_E2") (pintype "power_in"))
      (node (ref "SENSOR") (pin "G4") (pinfunction "VDD_RES_G4") (pintype "power_in"))
      (node (ref "TP8") (pin "TP") (pinfunction "TP_TP") (pintype "input"))
      (node (ref "X-NORTH") (pin "13") (pinfunction "13_13") (pintype "bidirectional"))
      (node (ref "X-NORTH") (pin "19") (pinfunction "19_19") (pintype "bidirectional"))
      (node (ref "X-NORTH") (pin "25") (pinfunction "25_25") (pintype "bidirectional"))
      (node (ref "X-NORTH") (pin "31") (pinfunction "31_31") (pintype "bidirectional"))
      (node (ref "X-NORTH") (pin "37") (pinfunction "37_37") (pintype "bidirectional"))
    )
    (net (code "107") (name "N_VW_CV") (class "Default")
      (node (ref "C8") (pin "1") (pinfunction "1_1") (pintype "passive"))
      (node (ref "R1") (pin "1") (pinfunction "1_1") (pintype "passive"))
      (node (ref "X-NORTH") (pin "2") (pinfunction "2_2") (pintype "bidirectional"))
    )
    (net (code "108") (name "N_VW_OV") (class "Default")
      (node (ref "UNW") (pin "7") (pinfunction "OUTB_7") (pintype "output"))
      (node (ref "X-NORTH") (pin "1") (pinfunction "1_1") (pintype "bidirectional"))
    )
    (net (code "109") (name "N_VW_UV") (class "Default")
      (node (ref "UNW") (pin "1") (pinfunction "OUTA_1") (pintype "output"))
      (node (ref "X-NORTH") (pin "7") (pinfunction "7_7") (pintype "bidirectional"))
    )
    (net (code "110") (name "Net-(SENSORB-CMDN)") (class "Default")
      (node (ref "C61") (pin "1") (pinfunction "1_1") (pintype "passive"))
      (node (ref "SENSOR") (pin "F1") (pinfunction "CMDN_F1") (pintype "bidirectional"))
    )
    (net (code "111") (name "Net-(SENSORB-CMDP)") (class "Default")
      (node (ref "C22") (pin "2") (pinfunction "2_2") (pintype "passive"))
      (node (ref "SENSOR") (pin "F2") (pinfunction "CMDP_F2") (pintype "bidirectional"))
    )
    (net (code "112") (name "Net-(SENSORB-CMDP_COMP)") (class "Default")
      (node (ref "C28") (pin "2") (pinfunction "2_2") (pintype "passive"))
      (node (ref "SENSOR") (pin "H3") (pinfunction "CMDP_COMP_H3") (pintype "bidirectional"))
    )
    (net (code "113") (name "Net-(SENSORB-CMDP_COMP_INV)") (class "Default")
      (node (ref "C27") (pin "2") (pinfunction "2_2") (pintype "passive"))
      (node (ref "SENSOR") (pin "F3") (pinfunction "CMDP_COMP_INV_F3") (pintype "bidirectional"))
    )
    (net (code "114") (name "Net-(SENSORB-CMD_COLAMP)") (class "Default")
      (node (ref "C25") (pin "2") (pinfunction "2_2") (pintype "passive"))
      (node (ref "SENSOR") (pin "C6") (pinfunction "CMD_COLAMP_C6") (pintype "bidirectional"))
    )
    (net (code "115") (name "Net-(SENSORB-CMD_COL_LOAD)") (class "Default")
      (node (ref "C23") (pin "2") (pinfunction "2_2") (pintype "passive"))
      (node (ref "SENSOR") (pin "B1") (pinfunction "CMD_COL_LOAD_B1") (pintype "bidirectional"))
    )
    (net (code "116") (name "Net-(SENSORB-CMD_COL_PC)") (class "Default")
      (node (ref "C26") (pin "2") (pinfunction "2_2") (pintype "passive"))
      (node (ref "SENSOR") (pin "D1") (pinfunction "CMD_COL_PC_D1") (pintype "bidirectional"))
    )
    (net (code "117") (name "Net-(SENSORB-CMD_LVDS)") (class "Default")
      (node (ref "C62") (pin "1") (pinfunction "1_1") (pintype "passive"))
      (node (ref "SENSOR") (pin "C1") (pinfunction "CMD_LVDS_C1") (pintype "bidirectional"))
    )
    (net (code "118") (name "Net-(SENSORB-CMD_RAMP)") (class "Default")
      (node (ref "C24") (pin "2") (pinfunction "2_2") (pintype "passive"))
      (node (ref "SENSOR") (pin "B29") (pinfunction "CMD_RAMP_B29") (pintype "bidirectional"))
    )
    (net (code "119") (name "Net-(SENSORB-VBGAP)") (class "Default")
      (node (ref "C64") (pin "1") (pinfunction "1_1") (pintype "passive"))
      (node (ref "SENSOR") (pin "C29") (pinfunction "VBGAP_C29") (pintype "bidirectional"))
    )
    (net (code "120") (name "Net-(SENSORB-VCLAMP)") (class "Default")
      (node (ref "C63") (pin "1") (pinfunction "1_1") (pintype "passive"))
      (node (ref "SENSOR") (pin "D4") (pinfunction "VCLAMP_D4") (pintype "bidirectional"))
    )
    (net (code "121") (name "Net-(SENSORB-VCLAMP_ADC)") (class "Default")
      (node (ref "C60") (pin "1") (pinfunction "1_1") (pintype "passive"))
      (node (ref "SENSOR") (pin "G2") (pinfunction "VCLAMP_ADC_G2") (pintype "bidirectional"))
    )
    (net (code "122") (name "Net-(SENSORB-VPCH_H)") (class "Default")
      (node (ref "C92") (pin "1") (pinfunction "1_1") (pintype "passive"))
      (node (ref "SENSOR") (pin "C4") (pinfunction "VPCH_H_C4") (pintype "bidirectional"))
    )
    (net (code "123") (name "Net-(SENSORB-VPCH_L)") (class "Default")
      (node (ref "C14") (pin "1") (pinfunction "1_1") (pintype "passive"))
      (node (ref "SENSOR") (pin "A4") (pinfunction "VPCH_L_A4") (pintype "bidirectional"))
    )
    (net (code "124") (name "Net-(SENSORB-VREF)") (class "Default")
      (node (ref "C29") (pin "1") (pinfunction "1_1") (pintype "passive"))
      (node (ref "SENSOR") (pin "A3") (pinfunction "VREF_A3") (pintype "bidirectional"))
    )
    (net (code "125") (name "Net-(SENSORB-VREF_ADC)") (class "Default")
      (node (ref "C30") (pin "1") (pinfunction "1_1") (pintype "passive"))
      (node (ref "SENSOR") (pin "B3") (pinfunction "VREF_ADC_B3") (pintype "bidirectional"))
    )
    (net (code "126") (name "Net-(SENSORB-VRES_L)") (class "Default")
      (node (ref "C15") (pin "1") (pinfunction "1_1") (pintype "passive"))
      (node (ref "SENSOR") (pin "D5") (pinfunction "VRES_L_D5") (pintype "bidirectional"))
    )
    (net (code "127") (name "Net-(SENSORB-VTF_LOW0)") (class "Default")
      (node (ref "C18") (pin "1") (pinfunction "1_1") (pintype "passive"))
      (node (ref "SENSOR") (pin "C5") (pinfunction "VTF_LOW0_C5") (pintype "bidirectional"))
    )
    (net (code "128") (name "Net-(SENSORB-VTF_LOW1)") (class "Default")
      (node (ref "C19") (pin "1") (pinfunction "1_1") (pintype "passive"))
      (node (ref "SENSOR") (pin "D6") (pinfunction "VTF_LOW1_D6") (pintype "bidirectional"))
    )
    (net (code "129") (name "Net-(SENSORB-VTF_LOW2)") (class "Default")
      (node (ref "C20") (pin "1") (pinfunction "1_1") (pintype "passive"))
      (node (ref "SENSOR") (pin "B30") (pinfunction "VTF_LOW2_B30") (pintype "bidirectional"))
    )
    (net (code "130") (name "Net-(SENSORB-VTF_LOW3)") (class "Default")
      (node (ref "C21") (pin "1") (pinfunction "1_1") (pintype "passive"))
      (node (ref "SENSOR") (pin "C30") (pinfunction "VTF_LOW3_C30") (pintype "bidirectional"))
    )
    (net (code "131") (name "Net-(U3-ADJ)") (class "Default")
      (node (ref "R21") (pin "1") (pinfunction "1_1") (pintype "passive"))
      (node (ref "R22") (pin "2") (pinfunction "2_2") (pintype "passive"))
      (node (ref "U3") (pin "5") (pinfunction "ADJ_5") (pintype "input"))
    )
    (net (code "132") (name "Net-(UEP-WP)") (class "Default")
      (node (ref "R1X") (pin "2") (pinfunction "2_2") (pintype "passive"))
      (node (ref "R2X") (pin "1") (pinfunction "1_1") (pintype "passive"))
      (node (ref "UEP") (pin "7") (pinfunction "WP_7") (pintype "input"))
    )
    (net (code "133") (name "Net-(UNE-VINA+)") (class "Default")
      (node (ref "R7") (pin "2") (pinfunction "2_2") (pintype "passive"))
      (node (ref "R8") (pin "1") (pinfunction "1_1") (pintype "passive"))
      (node (ref "UNE") (pin "3") (pinfunction "VINA+_3") (pintype "input"))
    )
    (net (code "134") (name "Net-(UNE-VINB-)") (class "Default")
      (node (ref "R8") (pin "2") (pinfunction "2_2") (pintype "passive"))
      (node (ref "R9") (pin "1") (pinfunction "1_1") (pintype "passive"))
      (node (ref "UNE") (pin "6") (pinfunction "VINB-_6") (pintype "input"))
    )
    (net (code "135") (name "Net-(UNN-VINA+)") (class "Default")
      (node (ref "R4") (pin "2") (pinfunction "2_2") (pintype "passive"))
      (node (ref "R5") (pin "1") (pinfunction "1_1") (pintype "passive"))
      (node (ref "UNN") (pin "3") (pinfunction "VINA+_3") (pintype "input"))
    )
    (net (code "136") (name "Net-(UNN-VINB-)") (class "Default")
      (node (ref "R5") (pin "2") (pinfunction "2_2") (pintype "passive"))
      (node (ref "R6") (pin "1") (pinfunction "1_1") (pintype "passive"))
      (node (ref "UNN") (pin "6") (pinfunction "VINB-_6") (pintype "input"))
    )
    (net (code "137") (name "Net-(UNW-VINA+)") (class "Default")
      (node (ref "R1") (pin "2") (pinfunction "2_2") (pintype "passive"))
      (node (ref "R2") (pin "1") (pinfunction "1_1") (pintype "passive"))
      (node (ref "UNW") (pin "3") (pinfunction "VINA+_3") (pintype "input"))
    )
    (net (code "138") (name "Net-(UNW-VINB-)") (class "Default")
      (node (ref "R2") (pin "2") (pinfunction "2_2") (pintype "passive"))
      (node (ref "R3") (pin "1") (pinfunction "1_1") (pintype "passive"))
      (node (ref "UNW") (pin "6") (pinfunction "VINB-_6") (pintype "input"))
    )
    (net (code "139") (name "Net-(USE-VINA+)") (class "Default")
      (node (ref "R10") (pin "2") (pinfunction "2_2") (pintype "passive"))
      (node (ref "R11") (pin "1") (pinfunction "1_1") (pintype "passive"))
      (node (ref "USE") (pin "3") (pinfunction "VINA+_3") (pintype "input"))
    )
    (net (code "140") (name "Net-(USE-VINB-)") (class "Default")
      (node (ref "R11") (pin "2") (pinfunction "2_2") (pintype "passive"))
      (node (ref "R12") (pin "1") (pinfunction "1_1") (pintype "passive"))
      (node (ref "USE") (pin "6") (pinfunction "VINB-_6") (pintype "input"))
    )
    (net (code "141") (name "Net-(USS-VINA+)") (class "Default")
      (node (ref "R13") (pin "2") (pinfunction "2_2") (pintype "passive"))
      (node (ref "R14") (pin "1") (pinfunction "1_1") (pintype "passive"))
      (node (ref "USS") (pin "3") (pinfunction "VINA+_3") (pintype "input"))
    )
    (net (code "142") (name "Net-(USS-VINB-)") (class "Default")
      (node (ref "R14") (pin "2") (pinfunction "2_2") (pintype "passive"))
      (node (ref "R15") (pin "1") (pinfunction "1_1") (pintype "passive"))
      (node (ref "USS") (pin "6") (pinfunction "VINB-_6") (pintype "input"))
    )
    (net (code "143") (name "Net-(USW-VINA+)") (class "Default")
      (node (ref "R16") (pin "2") (pinfunction "2_2") (pintype "passive"))
      (node (ref "R17") (pin "1") (pinfunction "1_1") (pintype "passive"))
      (node (ref "USW") (pin "3") (pinfunction "VINA+_3") (pintype "input"))
    )
    (net (code "144") (name "Net-(USW-VINB-)") (class "Default")
      (node (ref "R17") (pin "2") (pinfunction "2_2") (pintype "passive"))
      (node (ref "R18") (pin "1") (pinfunction "1_1") (pintype "passive"))
      (node (ref "USW") (pin "6") (pinfunction "VINB-_6") (pintype "input"))
    )
    (net (code "145") (name "S00_N") (class "Default")
      (node (ref "X-SOUTH") (pin "16") (pinfunction "16_16") (pintype "bidirectional"))
    )
    (net (code "146") (name "S00_P") (class "Default")
      (node (ref "X-SOUTH") (pin "14") (pinfunction "14_14") (pintype "bidirectional"))
    )
    (net (code "147") (name "S01_N") (class "Default")
      (node (ref "X-SOUTH") (pin "17") (pinfunction "17_17") (pintype "bidirectional"))
    )
    (net (code "148") (name "S01_P") (class "Default")
      (node (ref "X-SOUTH") (pin "15") (pinfunction "15_15") (pintype "bidirectional"))
    )
    (net (code "149") (name "S02_N") (class "Default")
      (node (ref "X-SOUTH") (pin "22") (pinfunction "22_22") (pintype "bidirectional"))
    )
    (net (code "150") (name "S02_P") (class "Default")
      (node (ref "X-SOUTH") (pin "20") (pinfunction "20_20") (pintype "bidirectional"))
    )
    (net (code "151") (name "S03_N") (class "Default")
      (node (ref "X-SOUTH") (pin "23") (pinfunction "23_23") (pintype "bidirectional"))
    )
    (net (code "152") (name "S03_P") (class "Default")
      (node (ref "X-SOUTH") (pin "21") (pinfunction "21_21") (pintype "bidirectional"))
    )
    (net (code "153") (name "S04_N") (class "Default")
      (node (ref "SENSOR") (pin "C24") (pinfunction "OUT32_N_C24") (pintype "output"))
      (node (ref "X-SOUTH") (pin "28") (pinfunction "28_28") (pintype "bidirectional"))
    )
    (net (code "154") (name "S04_P") (class "Default")
      (node (ref "SENSOR") (pin "C25") (pinfunction "OUT32_P_C25") (pintype "output"))
      (node (ref "X-SOUTH") (pin "26") (pinfunction "26_26") (pintype "bidirectional"))
    )
    (net (code "155") (name "S05_N") (class "Default")
      (node (ref "X-SOUTH") (pin "29") (pinfunction "29_29") (pintype "bidirectional"))
    )
    (net (code "156") (name "S05_P") (class "Default")
      (node (ref "X-SOUTH") (pin "27") (pinfunction "27_27") (pintype "bidirectional"))
    )
    (net (code "157") (name "S06_N") (class "Default")
      (node (ref "SENSOR") (pin "D23") (pinfunction "OUT30_N_D23") (pintype "output"))
      (node (ref "X-SOUTH") (pin "34") (pinfunction "34_34") (pintype "bidirectional"))
    )
    (net (code "158") (name "S06_P") (class "Default")
      (node (ref "SENSOR") (pin "D24") (pinfunction "OUT30_P_D24") (pintype "output"))
      (node (ref "X-SOUTH") (pin "32") (pinfunction "32_32") (pintype "bidirectional"))
    )
    (net (code "159") (name "S07_N") (class "Default")
      (node (ref "SENSOR") (pin "B24") (pinfunction "OUT31_N_B24") (pintype "output"))
      (node (ref "X-SOUTH") (pin "35") (pinfunction "35_35") (pintype "bidirectional"))
    )
    (net (code "160") (name "S07_P") (class "Default")
      (node (ref "SENSOR") (pin "B25") (pinfunction "OUT31_P_B25") (pintype "output"))
      (node (ref "X-SOUTH") (pin "33") (pinfunction "33_33") (pintype "bidirectional"))
    )
    (net (code "161") (name "S08_N") (class "Default")
      (node (ref "SENSOR") (pin "D21") (pinfunction "OUT27_N_D21") (pintype "output"))
      (node (ref "X-SOUTH") (pin "40") (pinfunction "40_40") (pintype "bidirectional"))
    )
    (net (code "162") (name "S08_P") (class "Default")
      (node (ref "SENSOR") (pin "D22") (pinfunction "OUT27_P_D22") (pintype "output"))
      (node (ref "X-SOUTH") (pin "38") (pinfunction "38_38") (pintype "bidirectional"))
    )
    (net (code "163") (name "S09_N") (class "Default")
      (node (ref "SENSOR") (pin "A23") (pinfunction "OUT29_N_A23") (pintype "output"))
      (node (ref "X-SOUTH") (pin "41") (pinfunction "41_41") (pintype "bidirectional"))
    )
    (net (code "164") (name "S09_P") (class "Default")
      (node (ref "SENSOR") (pin "A24") (pinfunction "OUT29_P_A24") (pintype "output"))
      (node (ref "X-SOUTH") (pin "39") (pinfunction "39_39") (pintype "bidirectional"))
    )
    (net (code "165") (name "S10_N") (class "Default")
      (node (ref "SENSOR") (pin "C21") (pinfunction "OUT28_N_C21") (pintype "output"))
      (node (ref "X-SOUTH") (pin "46") (pinfunction "46_46") (pintype "bidirectional"))
    )
    (net (code "166") (name "S10_P") (class "Default")
      (node (ref "SENSOR") (pin "C22") (pinfunction "OUT28_P_C22") (pintype "output"))
      (node (ref "X-SOUTH") (pin "44") (pinfunction "44_44") (pintype "bidirectional"))
    )
    (net (code "167") (name "S11_N") (class "Default")
      (node (ref "SENSOR") (pin "B20") (pinfunction "OUT26_N_B20") (pintype "output"))
      (node (ref "X-SOUTH") (pin "47") (pinfunction "47_47") (pintype "bidirectional"))
    )
    (net (code "168") (name "S11_P") (class "Default")
      (node (ref "SENSOR") (pin "B21") (pinfunction "OUT26_P_B21") (pintype "output"))
      (node (ref "X-SOUTH") (pin "45") (pinfunction "45_45") (pintype "bidirectional"))
    )
    (net (code "169") (name "S12_N") (class "Default")
      (node (ref "SENSOR") (pin "D19") (pinfunction "OUT24_N_D19") (pintype "output"))
      (node (ref "X-SOUTH") (pin "52") (pinfunction "52_52") (pintype "bidirectional"))
    )
    (net (code "170") (name "S12_P") (class "Default")
      (node (ref "SENSOR") (pin "D20") (pinfunction "OUT24_P_D20") (pintype "output"))
      (node (ref "X-SOUTH") (pin "50") (pinfunction "50_50") (pintype "bidirectional"))
    )
    (net (code "171") (name "S13_N") (class "Default")
      (node (ref "SENSOR") (pin "A19") (pinfunction "OUT23_N_A19") (pintype "output"))
      (node (ref "X-SOUTH") (pin "53") (pinfunction "53_53") (pintype "bidirectional"))
    )
    (net (code "172") (name "S13_P") (class "Default")
      (node (ref "SENSOR") (pin "A20") (pinfunction "OUT23_P_A20") (pintype "output"))
      (node (ref "X-SOUTH") (pin "51") (pinfunction "51_51") (pintype "bidirectional"))
    )
    (net (code "173") (name "S14_N") (class "Default")
      (node (ref "SENSOR") (pin "C19") (pinfunction "OUT25_N_C19") (pintype "output"))
      (node (ref "X-SOUTH") (pin "58") (pinfunction "58_58") (pintype "bidirectional"))
    )
    (net (code "174") (name "S14_P") (class "Default")
      (node (ref "SENSOR") (pin "C20") (pinfunction "OUT25_P_C20") (pintype "output"))
      (node (ref "X-SOUTH") (pin "56") (pinfunction "56_56") (pintype "bidirectional"))
    )
    (net (code "175") (name "S15_N") (class "Default")
      (node (ref "SENSOR") (pin "B18") (pinfunction "OUT22_N_B18") (pintype "output"))
      (node (ref "X-SOUTH") (pin "59") (pinfunction "59_59") (pintype "bidirectional"))
    )
    (net (code "176") (name "S15_P") (class "Default")
      (node (ref "SENSOR") (pin "B19") (pinfunction "OUT22_P_B19") (pintype "output"))
      (node (ref "X-SOUTH") (pin "57") (pinfunction "57_57") (pintype "bidirectional"))
    )
    (net (code "177") (name "S16_N") (class "Default")
      (node (ref "SENSOR") (pin "C17") (pinfunction "OUT21_N_C17") (pintype "output"))
      (node (ref "X-SOUTH") (pin "64") (pinfunction "64_64") (pintype "bidirectional"))
    )
    (net (code "178") (name "S16_P") (class "Default")
      (node (ref "SENSOR") (pin "C18") (pinfunction "OUT21_P_C18") (pintype "output"))
      (node (ref "X-SOUTH") (pin "62") (pinfunction "62_62") (pintype "bidirectional"))
    )
    (net (code "179") (name "S17_N") (class "Default")
      (node (ref "SENSOR") (pin "A17") (pinfunction "OUT19_N_A17") (pintype "output"))
      (node (ref "X-SOUTH") (pin "65") (pinfunction "65_65") (pintype "bidirectional"))
    )
    (net (code "180") (name "S17_P") (class "Default")
      (node (ref "SENSOR") (pin "A18") (pinfunction "OUT19_P_A18") (pintype "output"))
      (node (ref "X-SOUTH") (pin "63") (pinfunction "63_63") (pintype "bidirectional"))
    )
    (net (code "181") (name "S18_N") (class "Default")
      (node (ref "SENSOR") (pin "D17") (pinfunction "OUT20_N_D17") (pintype "output"))
      (node (ref "X-SOUTH") (pin "70") (pinfunction "70_70") (pintype "bidirectional"))
    )
    (net (code "182") (name "S18_P") (class "Default")
      (node (ref "SENSOR") (pin "D18") (pinfunction "OUT20_P_D18") (pintype "output"))
      (node (ref "X-SOUTH") (pin "68") (pinfunction "68_68") (pintype "bidirectional"))
    )
    (net (code "183") (name "S19_N") (class "Default")
      (node (ref "SENSOR") (pin "B16") (pinfunction "OUT18_N_B16") (pintype "output"))
      (node (ref "X-SOUTH") (pin "71") (pinfunction "71_71") (pintype "bidirectional"))
    )
    (net (code "184") (name "S19_P") (class "Default")
      (node (ref "SENSOR") (pin "B17") (pinfunction "OUT18_P_B17") (pintype "output"))
      (node (ref "X-SOUTH") (pin "69") (pinfunction "69_69") (pintype "bidirectional"))
    )
    (net (code "185") (name "S20_N") (class "Default")
      (node (ref "SENSOR") (pin "D15") (pinfunction "OUT17_N_D15") (pintype "output"))
      (node (ref "X-SOUTH") (pin "76") (pinfunction "76_76") (pintype "bidirectional"))
    )
    (net (code "186") (name "S20_P") (class "Default")
      (node (ref "SENSOR") (pin "D16") (pinfunction "OUT17_P_D16") (pintype "output"))
      (node (ref "X-SOUTH") (pin "74") (pinfunction "74_74") (pintype "bidirectional"))
    )
    (net (code "187") (name "S21_N") (class "Default")
      (node (ref "SENSOR") (pin "B14") (pinfunction "OUT16_N_B14") (pintype "output"))
      (node (ref "X-SOUTH") (pin "77") (pinfunction "77_77") (pintype "bidirectional"))
    )
    (net (code "188") (name "S21_P") (class "Default")
      (node (ref "SENSOR") (pin "B15") (pinfunction "OUT16_P_B15") (pintype "output"))
      (node (ref "X-SOUTH") (pin "75") (pinfunction "75_75") (pintype "bidirectional"))
    )
    (net (code "189") (name "S22_N") (class "Default")
      (node (ref "SENSOR") (pin "D13") (pinfunction "OUT15_N_D13") (pintype "output"))
      (node (ref "X-SOUTH") (pin "82") (pinfunction "82_82") (pintype "bidirectional"))
    )
    (net (code "190") (name "S22_P") (class "Default")
      (node (ref "SENSOR") (pin "D14") (pinfunction "OUT15_P_D14") (pintype "output"))
      (node (ref "X-SOUTH") (pin "80") (pinfunction "80_80") (pintype "bidirectional"))
    )
    (net (code "191") (name "S23_N") (class "Default")
      (node (ref "SENSOR") (pin "A13") (pinfunction "OUT13_N_A13") (pintype "output"))
      (node (ref "X-SOUTH") (pin "83") (pinfunction "83_83") (pintype "bidirectional"))
    )
    (net (code "192") (name "S23_P") (class "Default")
      (node (ref "SENSOR") (pin "A14") (pinfunction "OUT13_P_A14") (pintype "output"))
      (node (ref "X-SOUTH") (pin "81") (pinfunction "81_81") (pintype "bidirectional"))
    )
    (net (code "193") (name "S24_N") (class "Default")
      (node (ref "SENSOR") (pin "C13") (pinfunction "OUT14_N_C13") (pintype "output"))
      (node (ref "X-SOUTH") (pin "88") (pinfunction "88_88") (pintype "bidirectional"))
    )
    (net (code "194") (name "S24_P") (class "Default")
      (node (ref "SENSOR") (pin "C14") (pinfunction "OUT14_P_C14") (pintype "output"))
      (node (ref "X-SOUTH") (pin "86") (pinfunction "86_86") (pintype "bidirectional"))
    )
    (net (code "195") (name "S25_N") (class "Default")
      (node (ref "SENSOR") (pin "B12") (pinfunction "OUT12_N_B12") (pintype "output"))
      (node (ref "X-SOUTH") (pin "89") (pinfunction "89_89") (pintype "bidirectional"))
    )
    (net (code "196") (name "S25_P") (class "Default")
      (node (ref "SENSOR") (pin "B13") (pinfunction "OUT12_P_B13") (pintype "output"))
      (node (ref "X-SOUTH") (pin "87") (pinfunction "87_87") (pintype "bidirectional"))
    )
    (net (code "197") (name "S26_N") (class "Default")
      (node (ref "SENSOR") (pin "D11") (pinfunction "OUT10_N_D11") (pintype "output"))
      (node (ref "X-SOUTH") (pin "94") (pinfunction "94_94") (pintype "bidirectional"))
    )
    (net (code "198") (name "S26_P") (class "Default")
      (node (ref "SENSOR") (pin "D12") (pinfunction "OUT10_P_D12") (pintype "output"))
      (node (ref "X-SOUTH") (pin "92") (pinfunction "92_92") (pintype "bidirectional"))
    )
    (net (code "199") (name "S27_N") (class "Default")
      (node (ref "SENSOR") (pin "A11") (pinfunction "OUT9_N_A11") (pintype "output"))
      (node (ref "X-SOUTH") (pin "95") (pinfunction "95_95") (pintype "bidirectional"))
    )
    (net (code "200") (name "S27_P") (class "Default")
      (node (ref "SENSOR") (pin "A12") (pinfunction "OUT9_P_A12") (pintype "output"))
      (node (ref "X-SOUTH") (pin "93") (pinfunction "93_93") (pintype "bidirectional"))
    )
    (net (code "201") (name "S28_N") (class "Default")
      (node (ref "SENSOR") (pin "C11") (pinfunction "OUT11_N_C11") (pintype "output"))
      (node (ref "X-SOUTH") (pin "100") (pinfunction "100_100") (pintype "bidirectional"))
    )
    (net (code "202") (name "S28_P") (class "Default")
      (node (ref "SENSOR") (pin "C12") (pinfunction "OUT11_P_C12") (pintype "output"))
      (node (ref "X-SOUTH") (pin "98") (pinfunction "98_98") (pintype "bidirectional"))
    )
    (net (code "203") (name "S29_N") (class "Default")
      (node (ref "SENSOR") (pin "B10") (pinfunction "OUT8_N_B10") (pintype "output"))
      (node (ref "X-SOUTH") (pin "101") (pinfunction "101_101") (pintype "bidirectional"))
    )
    (net (code "204") (name "S29_P") (class "Default")
      (node (ref "SENSOR") (pin "B11") (pinfunction "OUT8_P_B11") (pintype "output"))
      (node (ref "X-SOUTH") (pin "99") (pinfunction "99_99") (pintype "bidirectional"))
    )
    (net (code "205") (name "S30_N") (class "Default")
      (node (ref "SENSOR") (pin "C9") (pinfunction "OUT7_N_C9") (pintype "output"))
      (node (ref "X-SOUTH") (pin "106") (pinfunction "106_106") (pintype "bidirectional"))
    )
    (net (code "206") (name "S30_P") (class "Default")
      (node (ref "SENSOR") (pin "C10") (pinfunction "OUT7_P_C10") (pintype "output"))
      (node (ref "X-SOUTH") (pin "104") (pinfunction "104_104") (pintype "bidirectional"))
    )
    (net (code "207") (name "S31_N") (class "Default")
      (node (ref "SENSOR") (pin "B8") (pinfunction "OUT5_N_B8") (pintype "output"))
      (node (ref "X-SOUTH") (pin "107") (pinfunction "107_107") (pintype "bidirectional"))
    )
    (net (code "208") (name "S31_P") (class "Default")
      (node (ref "SENSOR") (pin "B9") (pinfunction "OUT5_P_B9") (pintype "output"))
      (node (ref "X-SOUTH") (pin "105") (pinfunction "105_105") (pintype "bidirectional"))
    )
    (net (code "209") (name "S32_N") (class "Default")
      (node (ref "SENSOR") (pin "D9") (pinfunction "OUT6_N_D9") (pintype "output"))
      (node (ref "X-SOUTH") (pin "112") (pinfunction "112_112") (pintype "bidirectional"))
    )
    (net (code "210") (name "S32_P") (class "Default")
      (node (ref "SENSOR") (pin "D10") (pinfunction "OUT6_P_D10") (pintype "output"))
      (node (ref "X-SOUTH") (pin "110") (pinfunction "110_110") (pintype "bidirectional"))
    )
    (net (code "211") (name "S33_N") (class "Default")
      (node (ref "SENSOR") (pin "A7") (pinfunction "OUT2_N_A7") (pintype "output"))
      (node (ref "X-SOUTH") (pin "113") (pinfunction "113_113") (pintype "bidirectional"))
    )
    (net (code "212") (name "S33_P") (class "Default")
      (node (ref "SENSOR") (pin "A8") (pinfunction "OUT2_P_A8") (pintype "output"))
      (node (ref "X-SOUTH") (pin "111") (pinfunction "111_111") (pintype "bidirectional"))
    )
    (net (code "213") (name "S34_N") (class "Default")
      (node (ref "SENSOR") (pin "C7") (pinfunction "OUT4_N_C7") (pintype "output"))
      (node (ref "X-SOUTH") (pin "118") (pinfunction "118_118") (pintype "bidirectional"))
    )
    (net (code "214") (name "S34_P") (class "Default")
      (node (ref "SENSOR") (pin "C8") (pinfunction "OUT4_P_C8") (pintype "output"))
      (node (ref "X-SOUTH") (pin "116") (pinfunction "116_116") (pintype "bidirectional"))
    )
    (net (code "215") (name "S35_N") (class "Default")
      (node (ref "SENSOR") (pin "B6") (pinfunction "OUT1_N_B6") (pintype "output"))
      (node (ref "X-SOUTH") (pin "119") (pinfunction "119_119") (pintype "bidirectional"))
    )
    (net (code "216") (name "S35_P") (class "Default")
      (node (ref "SENSOR") (pin "B7") (pinfunction "OUT1_P_B7") (pintype "output"))
      (node (ref "X-SOUTH") (pin "117") (pinfunction "117_117") (pintype "bidirectional"))
    )
    (net (code "217") (name "S36_N") (class "Default")
      (node (ref "SENSOR") (pin "D7") (pinfunction "OUT3_N_D7") (pintype "output"))
      (node (ref "X-SOUTH") (pin "124") (pinfunction "124_124") (pintype "bidirectional"))
    )
    (net (code "218") (name "S36_P") (class "Default")
      (node (ref "SENSOR") (pin "D8") (pinfunction "OUT3_P_D8") (pintype "output"))
      (node (ref "X-SOUTH") (pin "122") (pinfunction "122_122") (pintype "bidirectional"))
    )
    (net (code "219") (name "S37_N") (class "Default")
      (node (ref "SENSOR") (pin "A5") (pinfunction "OUTCTR_N_A5") (pintype "output"))
      (node (ref "X-SOUTH") (pin "125") (pinfunction "125_125") (pintype "bidirectional"))
    )
    (net (code "220") (name "S37_P") (class "Default")
      (node (ref "SENSOR") (pin "A6") (pinfunction "OUTCTR_P_A6") (pintype "output"))
      (node (ref "X-SOUTH") (pin "123") (pinfunction "123_123") (pintype "bidirectional"))
    )
    (net (code "221") (name "S38_N") (class "Default")
      (node (ref "X-SOUTH") (pin "130") (pinfunction "130_130") (pintype "bidirectional"))
    )
    (net (code "222") (name "S38_P") (class "Default")
      (node (ref "X-SOUTH") (pin "128") (pinfunction "128_128") (pintype "bidirectional"))
    )
    (net (code "223") (name "S39_N") (class "Default")
      (node (ref "U3") (pin "6") (pinfunction "EN_6") (pintype "input"))
      (node (ref "X-SOUTH") (pin "131") (pinfunction "131_131") (pintype "bidirectional"))
    )
    (net (code "224") (name "S39_P") (class "Default")
      (node (ref "X-SOUTH") (pin "129") (pinfunction "129_129") (pintype "bidirectional"))
    )
    (net (code "225") (name "SPI_CLK") (class "Default")
      (node (ref "SENSOR") (pin "H29") (pinfunction "SPI_CLK_H29") (pintype "input"))
      (node (ref "U4") (pin "6") (pinfunction "1A1_6") (pintype "output"))
    )
    (net (code "226") (name "SPI_EN") (class "Default")
      (node (ref "SENSOR") (pin "F28") (pinfunction "SPI_EN_F28") (pintype "input"))
      (node (ref "U6") (pin "9") (pinfunction "B4_9") (pintype "bidirectional"))
    )
    (net (code "227") (name "SPI_IN") (class "Default")
      (node (ref "SENSOR") (pin "E28") (pinfunction "SPI_IN_E28") (pintype "input"))
      (node (ref "U4") (pin "7") (pinfunction "1A2_7") (pintype "output"))
    )
    (net (code "228") (name "SPI_OUT") (class "Default")
      (node (ref "SENSOR") (pin "G28") (pinfunction "SPI_OUT_G28") (pintype "output"))
      (node (ref "U4") (pin "8") (pinfunction "2A1_8") (pintype "output"))
    )
    (net (code "229") (name "SYS_RES_N") (class "Default")
      (node (ref "SENSOR") (pin "F30") (pinfunction "SYS_RES_N_F30") (pintype "input"))
      (node (ref "U5") (pin "10") (pinfunction "B3_10") (pintype "bidirectional"))
    )
    (net (code "230") (name "S_CHK_V") (class "Default")
      (node (ref "C5") (pin "1") (pinfunction "1_1") (pintype "passive"))
      (node (ref "C6") (pin "1") (pinfunction "1_1") (pintype "passive"))
      (node (ref "C7") (pin "1") (pinfunction "1_1") (pintype "passive"))
      (node (ref "R20") (pin "1") (pinfunction "1_1") (pintype "passive"))
      (node (ref "TP3") (pin "TP") (pinfunction "TP_TP") (pintype "input"))
      (node (ref "USE") (pin "8") (pinfunction "VDD_8") (pintype "power_in"))
      (node (ref "USS") (pin "8") (pinfunction "VDD_8") (pintype "power_in"))
      (node (ref "USW") (pin "8") (pinfunction "VDD_8") (pintype "power_in"))
      (node (ref "X-SOUTH") (pin "10") (pinfunction "10_10") (pintype "bidirectional"))
      (node (ref "X-SOUTH") (pin "8") (pinfunction "8_8") (pintype "bidirectional"))
    )
    (net (code "231") (name "S_I2C_V") (class "Default")
      (node (ref "X-SOUTH") (pin "135") (pinfunction "135_135") (pintype "bidirectional"))
      (node (ref "X-SOUTH") (pin "137") (pinfunction "137_137") (pintype "bidirectional"))
    )
    (net (code "232") (name "S_REF") (class "Default")
      (node (ref "R20") (pin "2") (pinfunction "2_2") (pintype "passive"))
      (node (ref "TP4") (pin "TP") (pinfunction "TP_TP") (pintype "input"))
      (node (ref "U2") (pin "3") (pinfunction "CATHODE_3") (pintype "output"))
      (node (ref "U2") (pin "4") (pinfunction "REF_4") (pintype "input"))
      (node (ref "USE") (pin "2") (pinfunction "VINA-_2") (pintype "input"))
      (node (ref "USE") (pin "5") (pinfunction "VINB+_5") (pintype "input"))
      (node (ref "USS") (pin "2") (pinfunction "VINA-_2") (pintype "input"))
      (node (ref "USS") (pin "5") (pinfunction "VINB+_5") (pintype "input"))
      (node (ref "USW") (pin "2") (pinfunction "VINA-_2") (pintype "input"))
      (node (ref "USW") (pin "5") (pinfunction "VINB+_5") (pintype "input"))
    )
    (net (code "233") (name "S_SCK") (class "Default")
      (node (ref "X-SOUTH") (pin "144") (pinfunction "144_144") (pintype "bidirectional"))
    )
    (net (code "234") (name "S_SCL") (class "Default")
      (node (ref "X-SOUTH") (pin "143") (pinfunction "143_143") (pintype "bidirectional"))
    )
    (net (code "235") (name "S_SDA") (class "Default")
      (node (ref "X-SOUTH") (pin "141") (pinfunction "141_141") (pintype "bidirectional"))
    )
    (net (code "236") (name "S_SDI") (class "Default")
      (node (ref "X-SOUTH") (pin "140") (pinfunction "140_140") (pintype "bidirectional"))
    )
    (net (code "237") (name "S_SDO") (class "Default")
      (node (ref "X-SOUTH") (pin "142") (pinfunction "142_142") (pintype "bidirectional"))
    )
    (net (code "238") (name "S_SPI_V") (class "Default")
      (node (ref "X-SOUTH") (pin "134") (pinfunction "134_134") (pintype "bidirectional"))
      (node (ref "X-SOUTH") (pin "136") (pinfunction "136_136") (pintype "bidirectional"))
    )
    (net (code "239") (name "S_VE") (class "Default")
      (node (ref "X-SOUTH") (pin "13") (pinfunction "13_13") (pintype "bidirectional"))
      (node (ref "X-SOUTH") (pin "19") (pinfunction "19_19") (pintype "bidirectional"))
      (node (ref "X-SOUTH") (pin "25") (pinfunction "25_25") (pintype "bidirectional"))
      (node (ref "X-SOUTH") (pin "31") (pinfunction "31_31") (pintype "bidirectional"))
      (node (ref "X-SOUTH") (pin "37") (pinfunction "37_37") (pintype "bidirectional"))
    )
    (net (code "240") (name "S_VE_CV") (class "Default")
      (node (ref "C11") (pin "1") (pinfunction "1_1") (pintype "passive"))
      (node (ref "R10") (pin "1") (pinfunction "1_1") (pintype "passive"))
      (node (ref "X-SOUTH") (pin "2") (pinfunction "2_2") (pintype "bidirectional"))
    )
    (net (code "241") (name "S_VE_OV") (class "Default")
      (node (ref "USE") (pin "7") (pinfunction "OUTB_7") (pintype "output"))
      (node (ref "X-SOUTH") (pin "1") (pinfunction "1_1") (pintype "bidirectional"))
    )
    (net (code "242") (name "S_VE_UV") (class "Default")
      (node (ref "USE") (pin "1") (pinfunction "OUTA_1") (pintype "output"))
      (node (ref "X-SOUTH") (pin "7") (pinfunction "7_7") (pintype "bidirectional"))
    )
    (net (code "243") (name "S_VS") (class "Default")
      (node (ref "C45") (pin "1") (pinfunction "1_1") (pintype "passive"))
      (node (ref "C46") (pin "1") (pinfunction "1_1") (pintype "passive"))
      (node (ref "C47") (pin "1") (pinfunction "1_1") (pintype "passive"))
      (node (ref "C48") (pin "1") (pinfunction "1_1") (pintype "passive"))
      (node (ref "C49") (pin "1") (pinfunction "1_1") (pintype "passive"))
      (node (ref "C72") (pin "1") (pinfunction "1_1") (pintype "passive"))
      (node (ref "C73") (pin "1") (pinfunction "1_1") (pintype "passive"))
      (node (ref "C74") (pin "1") (pinfunction "1_1") (pintype "passive"))
      (node (ref "C81") (pin "1") (pinfunction "1_1") (pintype "passive"))
      (node (ref "C82") (pin "1") (pinfunction "1_1") (pintype "passive"))
      (node (ref "C83") (pin "1") (pinfunction "1_1") (pintype "passive"))
      (node (ref "SENSOR") (pin "A30") (pinfunction "VDD_PIX_A30") (pintype "power_in"))
      (node (ref "SENSOR") (pin "D28") (pinfunction "VDD_PIX_D28") (pintype "power_in"))
      (node (ref "SENSOR") (pin "D30") (pinfunction "VDD_PIX_D30") (pintype "power_in"))
      (node (ref "SENSOR") (pin "G1") (pinfunction "VDD_PIX_G1") (pintype "power_in"))
      (node (ref "SENSOR") (pin "H28") (pinfunction "VDD_PIX_H28") (pintype "power_in"))
      (node (ref "TP6") (pin "TP") (pinfunction "TP_TP") (pintype "input"))
      (node (ref "X-SOUTH") (pin "49") (pinfunction "49_49") (pintype "bidirectional"))
      (node (ref "X-SOUTH") (pin "55") (pinfunction "55_55") (pintype "bidirectional"))
      (node (ref "X-SOUTH") (pin "61") (pinfunction "61_61") (pintype "bidirectional"))
      (node (ref "X-SOUTH") (pin "67") (pinfunction "67_67") (pintype "bidirectional"))
      (node (ref "X-SOUTH") (pin "73") (pinfunction "73_73") (pintype "bidirectional"))
      (node (ref "X-SOUTH") (pin "79") (pinfunction "79_79") (pintype "bidirectional"))
      (node (ref "X-SOUTH") (pin "85") (pinfunction "85_85") (pintype "bidirectional"))
      (node (ref "X-SOUTH") (pin "91") (pinfunction "91_91") (pintype "bidirectional"))
      (node (ref "X-SOUTH") (pin "97") (pinfunction "97_97") (pintype "bidirectional"))
    )
    (net (code "244") (name "S_VS_CV") (class "Default")
      (node (ref "C12") (pin "1") (pinfunction "1_1") (pintype "passive"))
      (node (ref "R13") (pin "1") (pinfunction "1_1") (pintype "passive"))
      (node (ref "X-SOUTH") (pin "4") (pinfunction "4_4") (pintype "bidirectional"))
    )
    (net (code "245") (name "S_VS_OV") (class "Default")
      (node (ref "USS") (pin "7") (pinfunction "OUTB_7") (pintype "output"))
      (node (ref "X-SOUTH") (pin "3") (pinfunction "3_3") (pintype "bidirectional"))
    )
    (net (code "246") (name "S_VS_UV") (class "Default")
      (node (ref "USS") (pin "1") (pinfunction "OUTA_1") (pintype "output"))
      (node (ref "X-SOUTH") (pin "9") (pinfunction "9_9") (pintype "bidirectional"))
    )
    (net (code "247") (name "S_VW") (class "Default")
      (node (ref "C90") (pin "1") (pinfunction "1_1") (pintype "passive"))
      (node (ref "U3") (pin "1") (pinfunction "BIAS_1") (pintype "power_in"))
      (node (ref "U3") (pin "3") (pinfunction "IN_3") (pintype "power_in"))
      (node (ref "X-SOUTH") (pin "109") (pinfunction "109_109") (pintype "bidirectional"))
      (node (ref "X-SOUTH") (pin "115") (pinfunction "115_115") (pintype "bidirectional"))
      (node (ref "X-SOUTH") (pin "121") (pinfunction "121_121") (pintype "bidirectional"))
      (node (ref "X-SOUTH") (pin "127") (pinfunction "127_127") (pintype "bidirectional"))
      (node (ref "X-SOUTH") (pin "133") (pinfunction "133_133") (pintype "bidirectional"))
    )
    (net (code "248") (name "S_VW_CV") (class "Default")
      (node (ref "C13") (pin "1") (pinfunction "1_1") (pintype "passive"))
      (node (ref "R16") (pin "1") (pinfunction "1_1") (pintype "passive"))
      (node (ref "X-SOUTH") (pin "6") (pinfunction "6_6") (pintype "bidirectional"))
    )
    (net (code "249") (name "S_VW_OV") (class "Default")
      (node (ref "USW") (pin "7") (pinfunction "OUTB_7") (pintype "output"))
      (node (ref "X-SOUTH") (pin "5") (pinfunction "5_5") (pintype "bidirectional"))
    )
    (net (code "250") (name "S_VW_UV") (class "Default")
      (node (ref "USW") (pin "1") (pinfunction "OUTA_1") (pintype "output"))
      (node (ref "X-SOUTH") (pin "11") (pinfunction "11_11") (pintype "bidirectional"))
    )
    (net (code "251") (name "TDIG1") (class "Default")
      (node (ref "SENSOR") (pin "G27") (pinfunction "TDIG1_G27") (pintype "output"))
      (node (ref "U5") (pin "9") (pinfunction "B4_9") (pintype "bidirectional"))
    )
    (net (code "252") (name "TDIG2") (class "Default")
      (node (ref "SENSOR") (pin "G26") (pinfunction "TDIG2_G26") (pintype "output"))
      (node (ref "U6") (pin "11") (pinfunction "B2_11") (pintype "bidirectional"))
    )
    (net (code "253") (name "T_EXP1") (class "Default")
      (node (ref "SENSOR") (pin "H30") (pinfunction "T_EXP1_H30") (pintype "input"))
      (node (ref "U5") (pin "12") (pinfunction "B1_12") (pintype "bidirectional"))
    )
    (net (code "254") (name "T_EXP2") (class "Default")
      (node (ref "SENSOR") (pin "E29") (pinfunction "T_EXP2_E29") (pintype "input"))
      (node (ref "U6") (pin "10") (pinfunction "B3_10") (pintype "bidirectional"))
    )
    (net (code "255") (name "VRAMP1") (class "Default")
      (node (ref "C16") (pin "1") (pinfunction "1_1") (pintype "passive"))
      (node (ref "R23") (pin "1") (pinfunction "1_1") (pintype "passive"))
      (node (ref "SENSOR") (pin "G29") (pinfunction "VRAMP1_G29") (pintype "bidirectional"))
    )
    (net (code "256") (name "VRAMP2") (class "Default")
      (node (ref "C17") (pin "1") (pinfunction "1_1") (pintype "passive"))
      (node (ref "R23") (pin "2") (pinfunction "2_2") (pintype "passive"))
      (node (ref "SENSOR") (pin "F29") (pinfunction "VRAMP2_F29") (pintype "bidirectional"))
    )
    (net (code "257") (name "VTREF") (class "Default")
      (node (ref "C65") (pin "1") (pinfunction "1_1") (pintype "passive"))
      (node (ref "C91") (pin "2") (pinfunction "2_2") (pintype "passive"))
      (node (ref "R21") (pin "2") (pinfunction "2_2") (pintype "passive"))
      (node (ref "R24") (pin "1") (pinfunction "1_1") (pintype "passive"))
      (node (ref "SENSOR") (pin "B2") (pinfunction "VTREF_B2") (pintype "bidirectional"))
      (node (ref "U3") (pin "4") (pinfunction "OUT_4") (pintype "power_in"))
    )
    (net (code "258") (name "VTSIG") (class "Default")
      (node (ref "C66") (pin "1") (pinfunction "1_1") (pintype "passive"))
      (node (ref "R24") (pin "2") (pinfunction "2_2") (pintype "passive"))
      (node (ref "SENSOR") (pin "C2") (pinfunction "VTSIG_C2") (pintype "bidirectional"))
    )
    (net (code "259") (name "unconnected-(U1-NC-Pad1)") (class "Default")
      (node (ref "U1") (pin "1") (pinfunction "NC_1") (pintype "no_connect"))
    )
    (net (code "260") (name "unconnected-(U1-NC-Pad2)") (class "Default")
      (node (ref "U1") (pin "2") (pinfunction "NC_2") (pintype "no_connect"))
    )
    (net (code "261") (name "unconnected-(U2-NC-Pad1)") (class "Default")
      (node (ref "U2") (pin "1") (pinfunction "NC_1") (pintype "no_connect"))
    )
    (net (code "262") (name "unconnected-(U2-NC-Pad2)") (class "Default")
      (node (ref "U2") (pin "2") (pinfunction "NC_2") (pintype "no_connect"))
    )
    (net (code "263") (name "unconnected-(U4-2B2-Pad12)") (class "Default")
      (node (ref "U4") (pin "12") (pinfunction "2B2_12") (pintype "output"))
    )
    (net (code "264") (name "unconnected-(X-NORTH-PadM1)") (class "Default")
      (node (ref "X-NORTH") (pin "M1") (pinfunction "M1_M1") (pintype "bidirectional"))
    )
    (net (code "265") (name "unconnected-(X-NORTH-PadM2)") (class "Default")
      (node (ref "X-NORTH") (pin "M2") (pinfunction "M2_M2") (pintype "bidirectional"))
    )
    (net (code "266") (name "unconnected-(X-SOUTH-PadM1)") (class "Default")
      (node (ref "X-SOUTH") (pin "M1") (pinfunction "M1_M1") (pintype "bidirectional"))
    )
    (net (code "267") (name "unconnected-(X-SOUTH-PadM2)") (class "Default")
      (node (ref "X-SOUTH") (pin "M2") (pinfunction "M2_M2") (pintype "bidirectional"))
    )
  )
)
